# tempDAQ.net
KiCad netlist of a schematic drawn in EAGLE
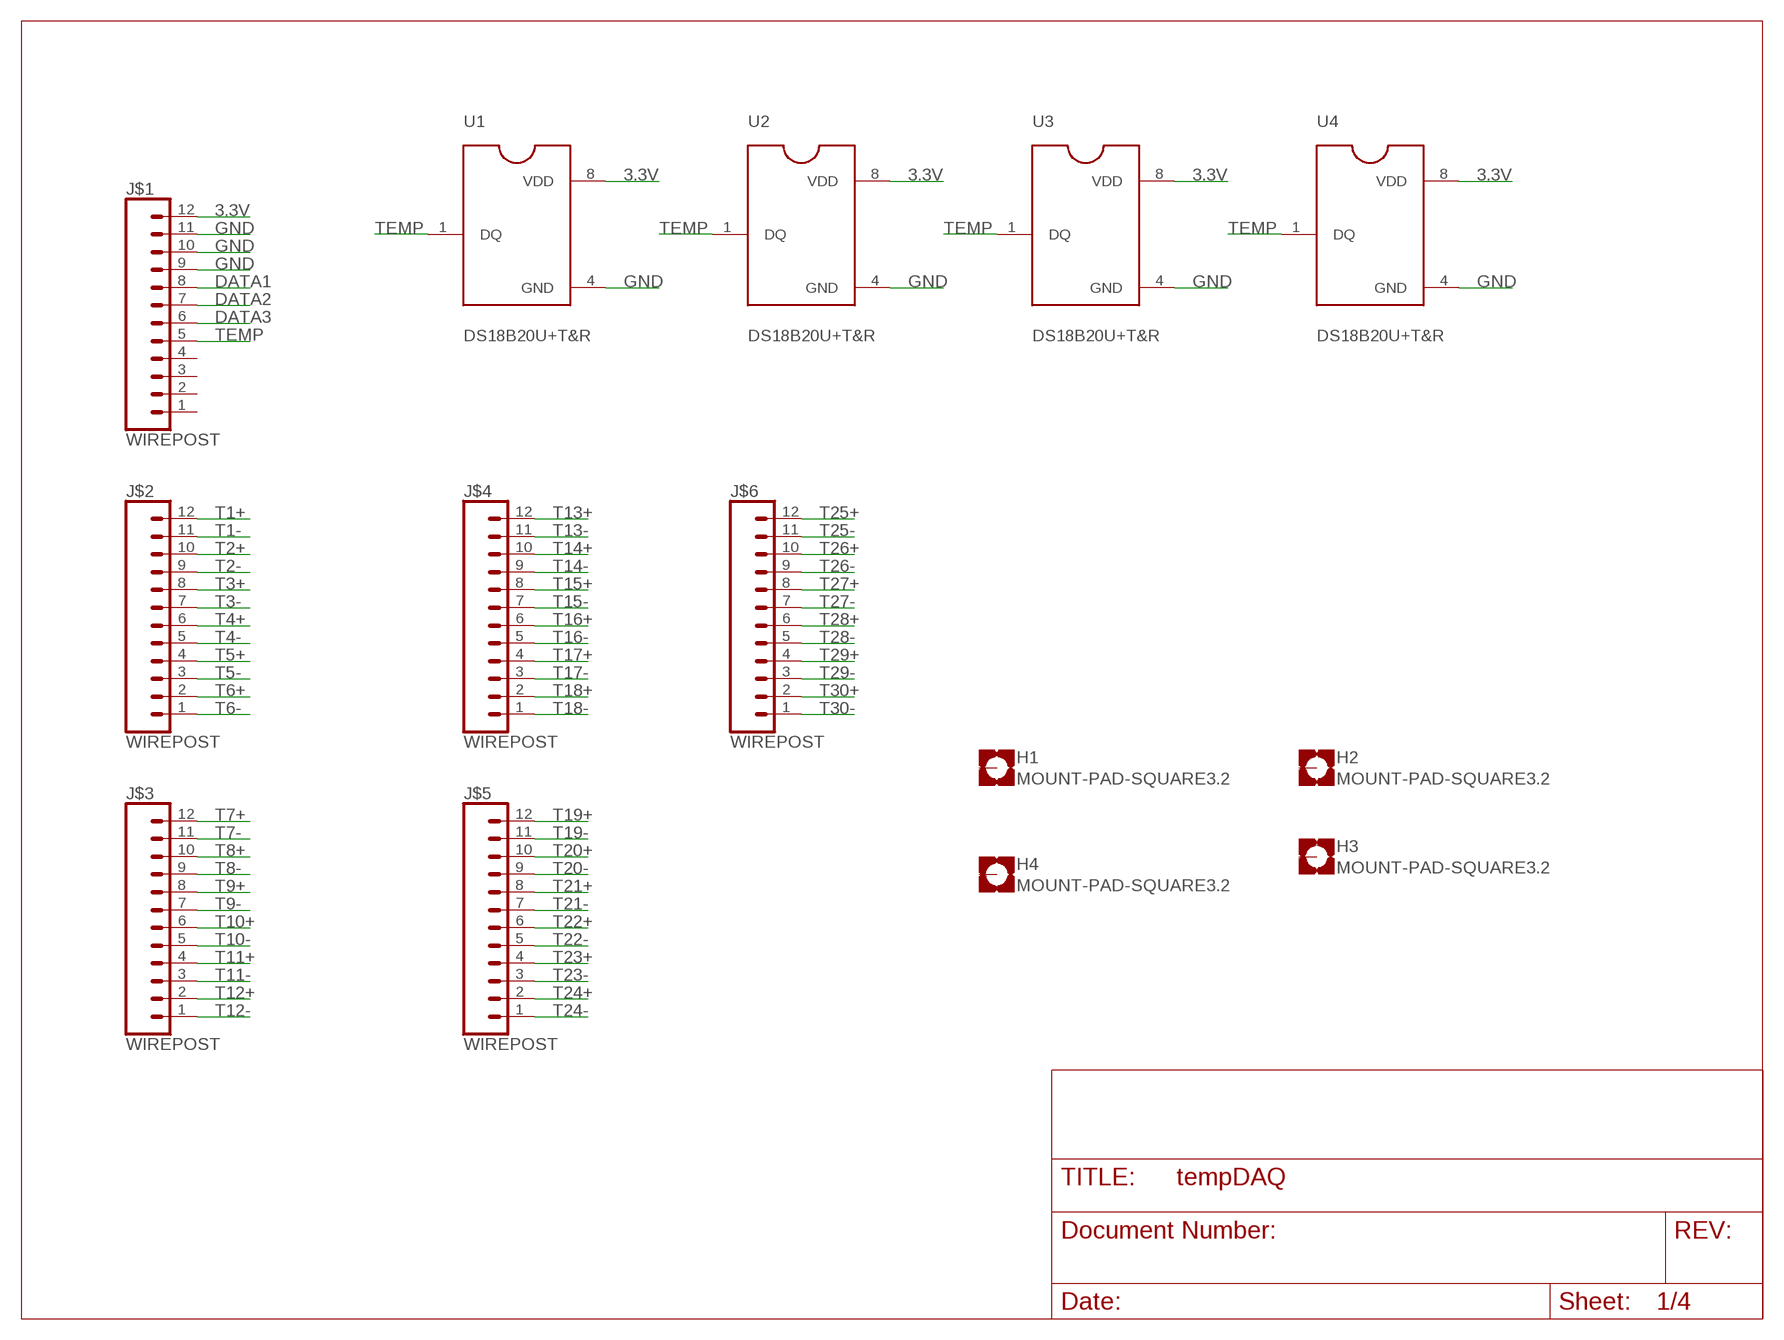
[diagram p0: schematic, sheet 1]
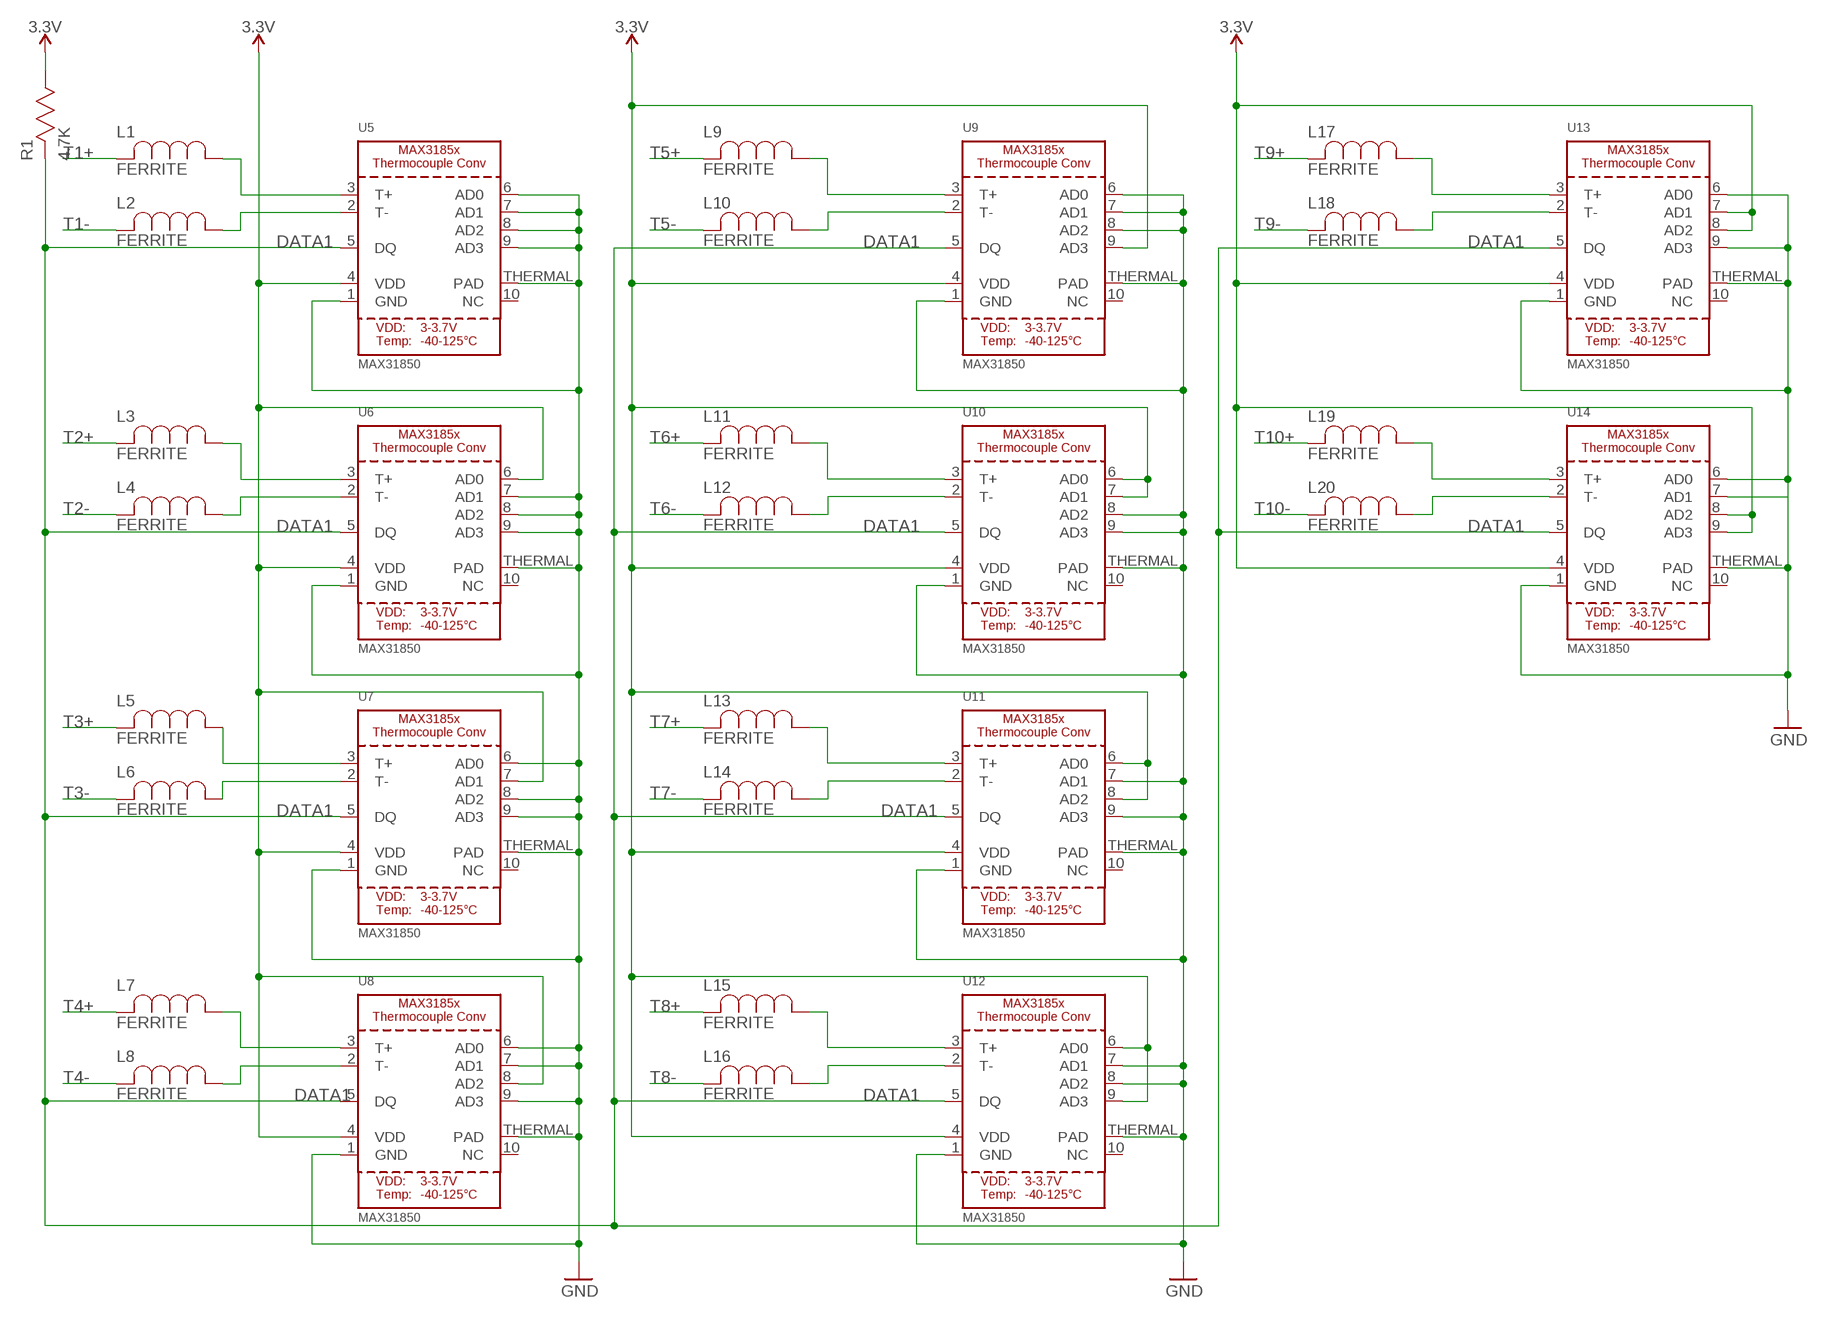
[diagram p1: schematic, sheet 2]
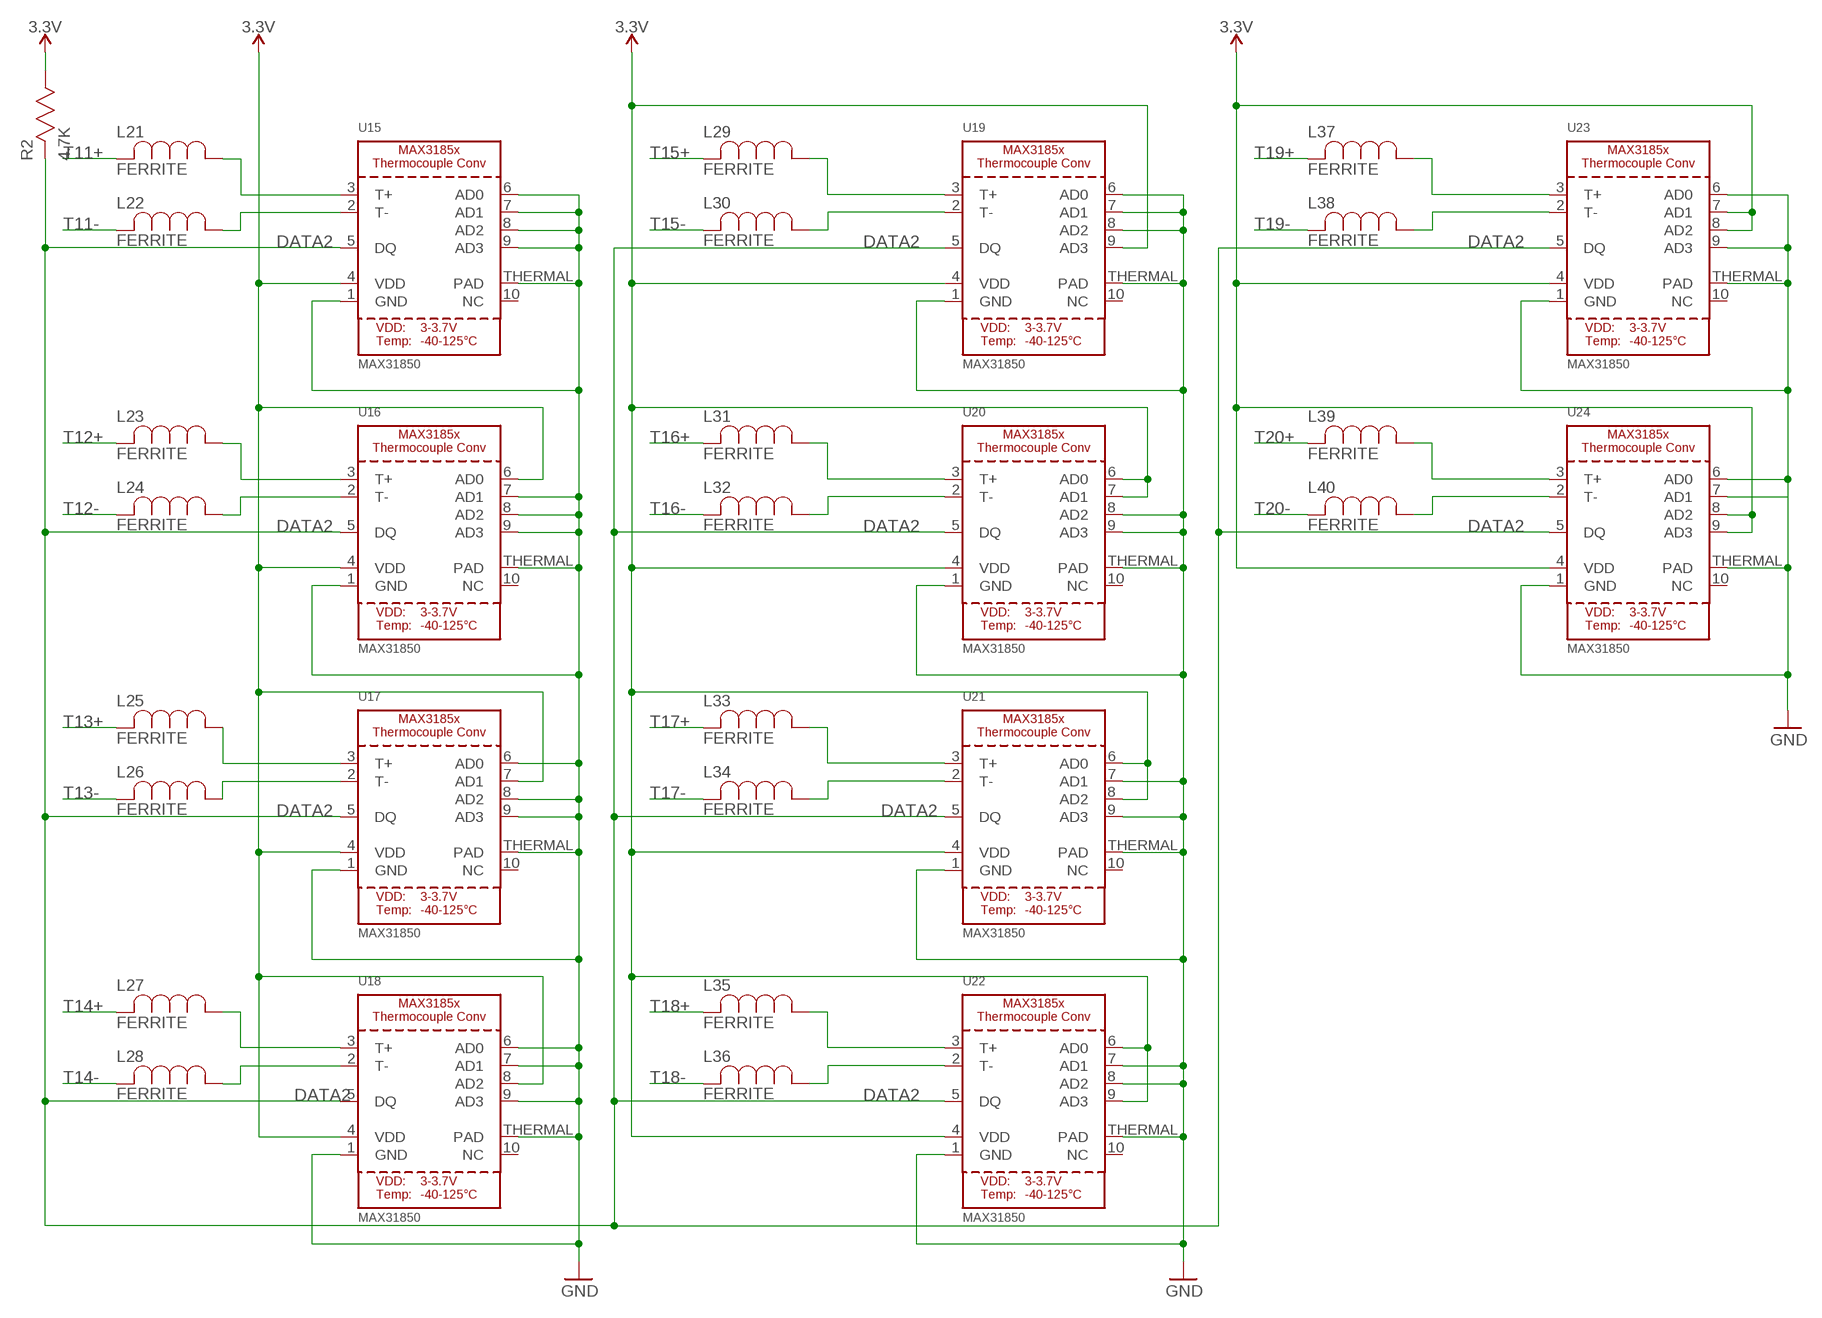
[diagram p2: schematic, sheet 3]
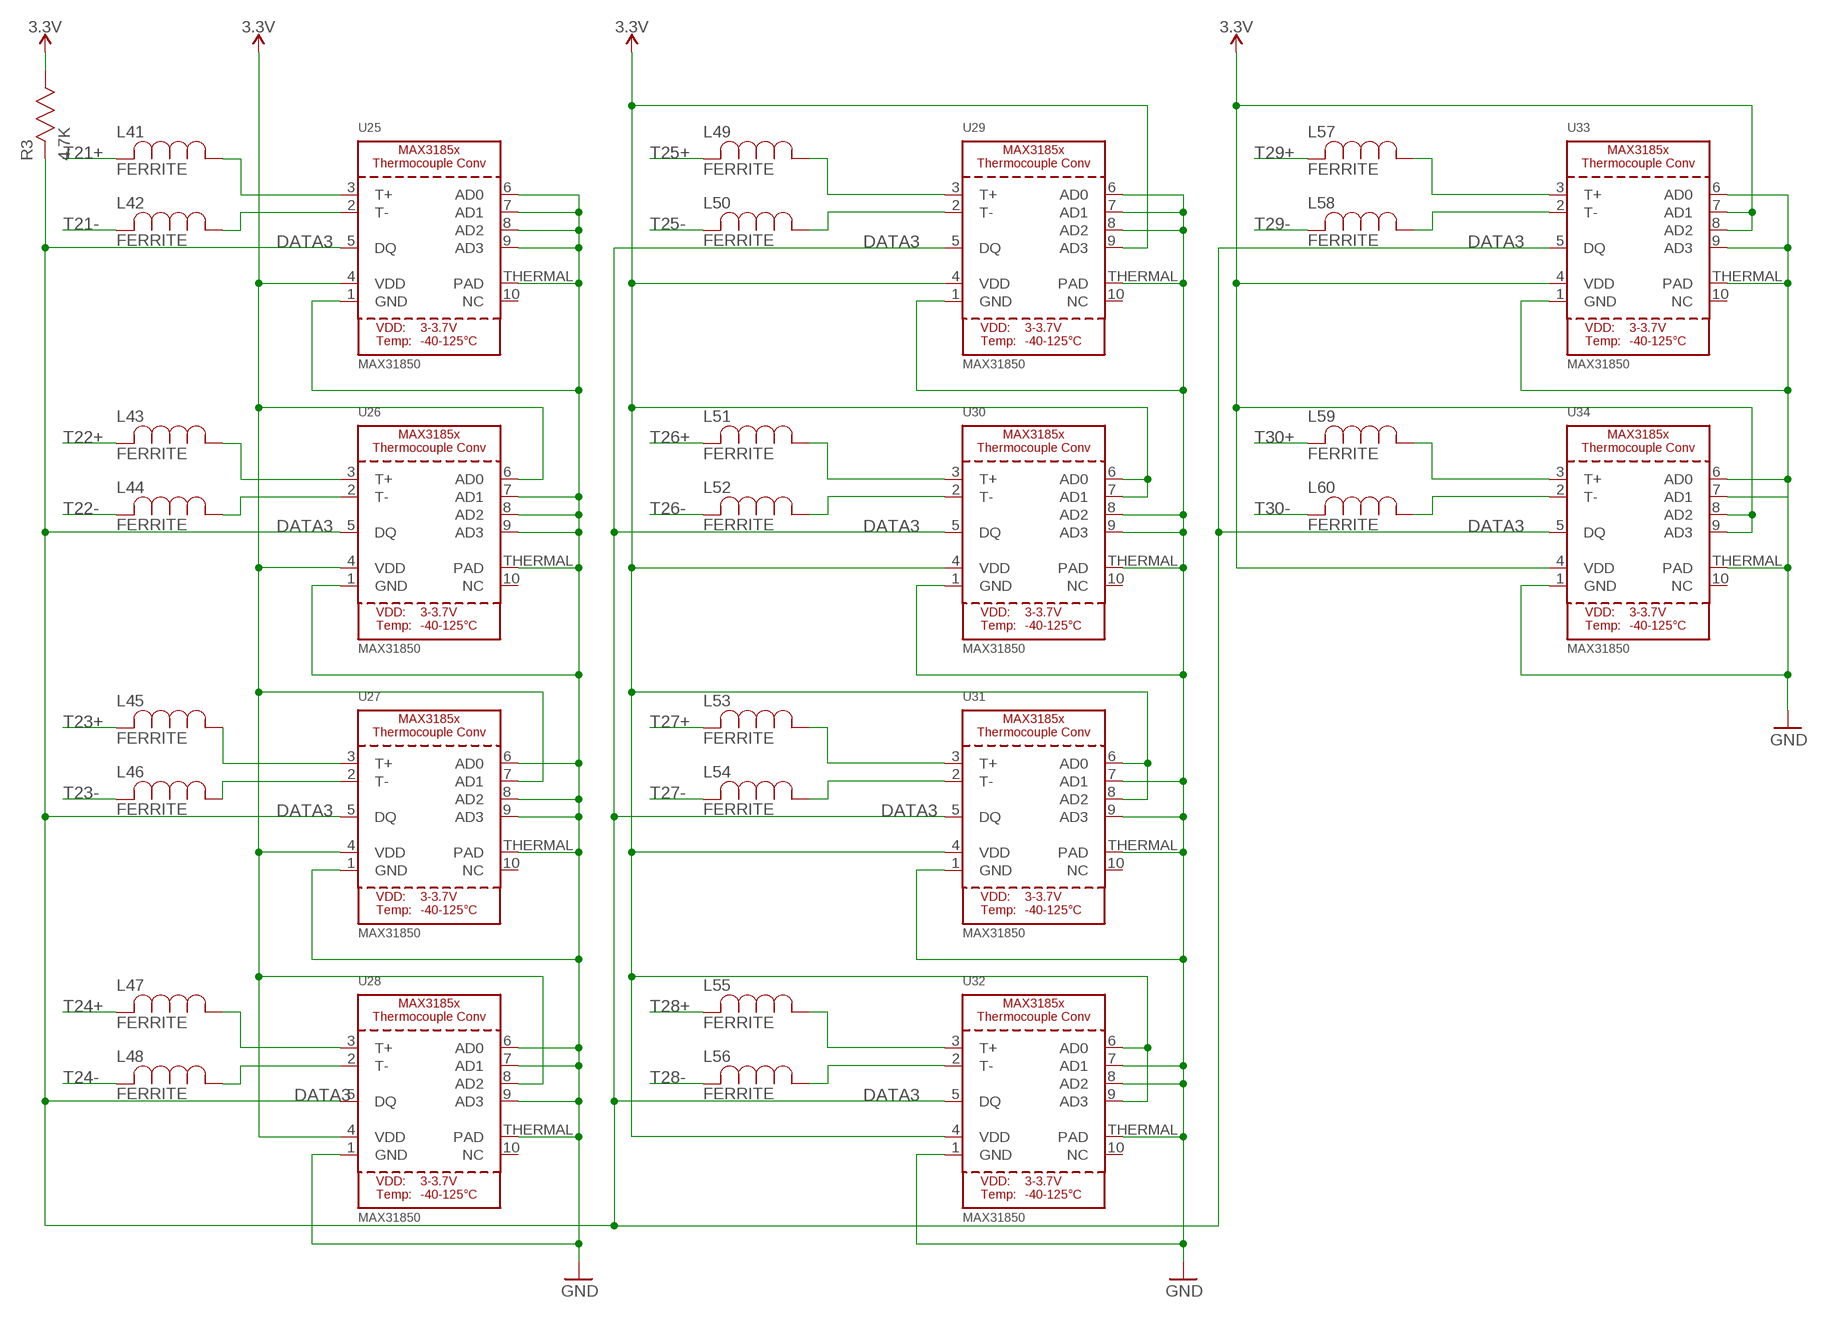
[diagram p3: schematic, sheet 4]

(export (version "E")
  (design (tool "Eeschema 10.0.6"))
  (components
    (comp (ref "L21")
      (value "FERRITE")
      (footprint "eagle-import:IND_BOURNS_MH2029")
      (fields (field (name "MANUFACTURER_PART_NUMBER") "MH2029300Y"))
      (libsource (lib "eagle-import") (part "FERRITE"))
    )
    (comp (ref "L22")
      (value "FERRITE")
      (footprint "eagle-import:IND_BOURNS_MH2029")
      (fields (field (name "MANUFACTURER_PART_NUMBER") "MH2029300Y"))
      (libsource (lib "eagle-import") (part "FERRITE"))
    )
    (comp (ref "L23")
      (value "FERRITE")
      (footprint "eagle-import:IND_BOURNS_MH2029")
      (fields (field (name "MANUFACTURER_PART_NUMBER") "MH2029300Y"))
      (libsource (lib "eagle-import") (part "FERRITE"))
    )
    (comp (ref "L24")
      (value "FERRITE")
      (footprint "eagle-import:IND_BOURNS_MH2029")
      (fields (field (name "MANUFACTURER_PART_NUMBER") "MH2029300Y"))
      (libsource (lib "eagle-import") (part "FERRITE"))
    )
    (comp (ref "L25")
      (value "FERRITE")
      (footprint "eagle-import:IND_BOURNS_MH2029")
      (fields (field (name "MANUFACTURER_PART_NUMBER") "MH2029300Y"))
      (libsource (lib "eagle-import") (part "FERRITE"))
    )
    (comp (ref "L26")
      (value "FERRITE")
      (footprint "eagle-import:IND_BOURNS_MH2029")
      (fields (field (name "MANUFACTURER_PART_NUMBER") "MH2029300Y"))
      (libsource (lib "eagle-import") (part "FERRITE"))
    )
    (comp (ref "L27")
      (value "FERRITE")
      (footprint "eagle-import:IND_BOURNS_MH2029")
      (fields (field (name "MANUFACTURER_PART_NUMBER") "MH2029300Y"))
      (libsource (lib "eagle-import") (part "FERRITE"))
    )
    (comp (ref "L28")
      (value "FERRITE")
      (footprint "eagle-import:IND_BOURNS_MH2029")
      (fields (field (name "MANUFACTURER_PART_NUMBER") "MH2029300Y"))
      (libsource (lib "eagle-import") (part "FERRITE"))
    )
    (comp (ref "L29")
      (value "FERRITE")
      (footprint "eagle-import:IND_BOURNS_MH2029")
      (fields (field (name "MANUFACTURER_PART_NUMBER") "MH2029300Y"))
      (libsource (lib "eagle-import") (part "FERRITE"))
    )
    (comp (ref "L30")
      (value "FERRITE")
      (footprint "eagle-import:IND_BOURNS_MH2029")
      (fields (field (name "MANUFACTURER_PART_NUMBER") "MH2029300Y"))
      (libsource (lib "eagle-import") (part "FERRITE"))
    )
    (comp (ref "L31")
      (value "FERRITE")
      (footprint "eagle-import:IND_BOURNS_MH2029")
      (fields (field (name "MANUFACTURER_PART_NUMBER") "MH2029300Y"))
      (libsource (lib "eagle-import") (part "FERRITE"))
    )
    (comp (ref "L32")
      (value "FERRITE")
      (footprint "eagle-import:IND_BOURNS_MH2029")
      (fields (field (name "MANUFACTURER_PART_NUMBER") "MH2029300Y"))
      (libsource (lib "eagle-import") (part "FERRITE"))
    )
    (comp (ref "L33")
      (value "FERRITE")
      (footprint "eagle-import:IND_BOURNS_MH2029")
      (fields (field (name "MANUFACTURER_PART_NUMBER") "MH2029300Y"))
      (libsource (lib "eagle-import") (part "FERRITE"))
    )
    (comp (ref "L34")
      (value "FERRITE")
      (footprint "eagle-import:IND_BOURNS_MH2029")
      (fields (field (name "MANUFACTURER_PART_NUMBER") "MH2029300Y"))
      (libsource (lib "eagle-import") (part "FERRITE"))
    )
    (comp (ref "L35")
      (value "FERRITE")
      (footprint "eagle-import:IND_BOURNS_MH2029")
      (fields (field (name "MANUFACTURER_PART_NUMBER") "MH2029300Y"))
      (libsource (lib "eagle-import") (part "FERRITE"))
    )
    (comp (ref "L36")
      (value "FERRITE")
      (footprint "eagle-import:IND_BOURNS_MH2029")
      (fields (field (name "MANUFACTURER_PART_NUMBER") "MH2029300Y"))
      (libsource (lib "eagle-import") (part "FERRITE"))
    )
    (comp (ref "L37")
      (value "FERRITE")
      (footprint "eagle-import:IND_BOURNS_MH2029")
      (fields (field (name "MANUFACTURER_PART_NUMBER") "MH2029300Y"))
      (libsource (lib "eagle-import") (part "FERRITE"))
    )
    (comp (ref "L38")
      (value "FERRITE")
      (footprint "eagle-import:IND_BOURNS_MH2029")
      (fields (field (name "MANUFACTURER_PART_NUMBER") "MH2029300Y"))
      (libsource (lib "eagle-import") (part "FERRITE"))
    )
    (comp (ref "L39")
      (value "FERRITE")
      (footprint "eagle-import:IND_BOURNS_MH2029")
      (fields (field (name "MANUFACTURER_PART_NUMBER") "MH2029300Y"))
      (libsource (lib "eagle-import") (part "FERRITE"))
    )
    (comp (ref "L40")
      (value "FERRITE")
      (footprint "eagle-import:IND_BOURNS_MH2029")
      (fields (field (name "MANUFACTURER_PART_NUMBER") "MH2029300Y"))
      (libsource (lib "eagle-import") (part "FERRITE"))
    )
    (comp (ref "R2")
      (value "4.7K")
      (footprint "eagle-import:RC0603N")
      (libsource (lib "eagle-import") (part "RES_4_7K"))
    )
    (comp (ref "U15")
      (value "MAX31850")
      (footprint "eagle-import:TDFN10_3X4MM")
      (libsource (lib "eagle-import") (part "MAX3185X"))
    )
    (comp (ref "U16")
      (value "MAX31850")
      (footprint "eagle-import:TDFN10_3X4MM")
      (libsource (lib "eagle-import") (part "MAX3185X"))
    )
    (comp (ref "U17")
      (value "MAX31850")
      (footprint "eagle-import:TDFN10_3X4MM")
      (libsource (lib "eagle-import") (part "MAX3185X"))
    )
    (comp (ref "U18")
      (value "MAX31850")
      (footprint "eagle-import:TDFN10_3X4MM")
      (libsource (lib "eagle-import") (part "MAX3185X"))
    )
    (comp (ref "U19")
      (value "MAX31850")
      (footprint "eagle-import:TDFN10_3X4MM")
      (libsource (lib "eagle-import") (part "MAX3185X"))
    )
    (comp (ref "U20")
      (value "MAX31850")
      (footprint "eagle-import:TDFN10_3X4MM")
      (libsource (lib "eagle-import") (part "MAX3185X"))
    )
    (comp (ref "U21")
      (value "MAX31850")
      (footprint "eagle-import:TDFN10_3X4MM")
      (libsource (lib "eagle-import") (part "MAX3185X"))
    )
    (comp (ref "U22")
      (value "MAX31850")
      (footprint "eagle-import:TDFN10_3X4MM")
      (libsource (lib "eagle-import") (part "MAX3185X"))
    )
    (comp (ref "U23")
      (value "MAX31850")
      (footprint "eagle-import:TDFN10_3X4MM")
      (libsource (lib "eagle-import") (part "MAX3185X"))
    )
    (comp (ref "U24")
      (value "MAX31850")
      (footprint "eagle-import:TDFN10_3X4MM")
      (libsource (lib "eagle-import") (part "MAX3185X"))
    )
    (comp (ref "L41")
      (value "FERRITE")
      (footprint "eagle-import:IND_BOURNS_MH2029")
      (fields (field (name "MANUFACTURER_PART_NUMBER") "MH2029300Y"))
      (libsource (lib "eagle-import") (part "FERRITE"))
    )
    (comp (ref "L42")
      (value "FERRITE")
      (footprint "eagle-import:IND_BOURNS_MH2029")
      (fields (field (name "MANUFACTURER_PART_NUMBER") "MH2029300Y"))
      (libsource (lib "eagle-import") (part "FERRITE"))
    )
    (comp (ref "L43")
      (value "FERRITE")
      (footprint "eagle-import:IND_BOURNS_MH2029")
      (fields (field (name "MANUFACTURER_PART_NUMBER") "MH2029300Y"))
      (libsource (lib "eagle-import") (part "FERRITE"))
    )
    (comp (ref "L44")
      (value "FERRITE")
      (footprint "eagle-import:IND_BOURNS_MH2029")
      (fields (field (name "MANUFACTURER_PART_NUMBER") "MH2029300Y"))
      (libsource (lib "eagle-import") (part "FERRITE"))
    )
    (comp (ref "L45")
      (value "FERRITE")
      (footprint "eagle-import:IND_BOURNS_MH2029")
      (fields (field (name "MANUFACTURER_PART_NUMBER") "MH2029300Y"))
      (libsource (lib "eagle-import") (part "FERRITE"))
    )
    (comp (ref "L46")
      (value "FERRITE")
      (footprint "eagle-import:IND_BOURNS_MH2029")
      (fields (field (name "MANUFACTURER_PART_NUMBER") "MH2029300Y"))
      (libsource (lib "eagle-import") (part "FERRITE"))
    )
    (comp (ref "L47")
      (value "FERRITE")
      (footprint "eagle-import:IND_BOURNS_MH2029")
      (fields (field (name "MANUFACTURER_PART_NUMBER") "MH2029300Y"))
      (libsource (lib "eagle-import") (part "FERRITE"))
    )
    (comp (ref "L48")
      (value "FERRITE")
      (footprint "eagle-import:IND_BOURNS_MH2029")
      (fields (field (name "MANUFACTURER_PART_NUMBER") "MH2029300Y"))
      (libsource (lib "eagle-import") (part "FERRITE"))
    )
    (comp (ref "L49")
      (value "FERRITE")
      (footprint "eagle-import:IND_BOURNS_MH2029")
      (fields (field (name "MANUFACTURER_PART_NUMBER") "MH2029300Y"))
      (libsource (lib "eagle-import") (part "FERRITE"))
    )
    (comp (ref "L50")
      (value "FERRITE")
      (footprint "eagle-import:IND_BOURNS_MH2029")
      (fields (field (name "MANUFACTURER_PART_NUMBER") "MH2029300Y"))
      (libsource (lib "eagle-import") (part "FERRITE"))
    )
    (comp (ref "L51")
      (value "FERRITE")
      (footprint "eagle-import:IND_BOURNS_MH2029")
      (fields (field (name "MANUFACTURER_PART_NUMBER") "MH2029300Y"))
      (libsource (lib "eagle-import") (part "FERRITE"))
    )
    (comp (ref "L52")
      (value "FERRITE")
      (footprint "eagle-import:IND_BOURNS_MH2029")
      (fields (field (name "MANUFACTURER_PART_NUMBER") "MH2029300Y"))
      (libsource (lib "eagle-import") (part "FERRITE"))
    )
    (comp (ref "L53")
      (value "FERRITE")
      (footprint "eagle-import:IND_BOURNS_MH2029")
      (fields (field (name "MANUFACTURER_PART_NUMBER") "MH2029300Y"))
      (libsource (lib "eagle-import") (part "FERRITE"))
    )
    (comp (ref "L54")
      (value "FERRITE")
      (footprint "eagle-import:IND_BOURNS_MH2029")
      (fields (field (name "MANUFACTURER_PART_NUMBER") "MH2029300Y"))
      (libsource (lib "eagle-import") (part "FERRITE"))
    )
    (comp (ref "L55")
      (value "FERRITE")
      (footprint "eagle-import:IND_BOURNS_MH2029")
      (fields (field (name "MANUFACTURER_PART_NUMBER") "MH2029300Y"))
      (libsource (lib "eagle-import") (part "FERRITE"))
    )
    (comp (ref "L56")
      (value "FERRITE")
      (footprint "eagle-import:IND_BOURNS_MH2029")
      (fields (field (name "MANUFACTURER_PART_NUMBER") "MH2029300Y"))
      (libsource (lib "eagle-import") (part "FERRITE"))
    )
    (comp (ref "L57")
      (value "FERRITE")
      (footprint "eagle-import:IND_BOURNS_MH2029")
      (fields (field (name "MANUFACTURER_PART_NUMBER") "MH2029300Y"))
      (libsource (lib "eagle-import") (part "FERRITE"))
    )
    (comp (ref "L58")
      (value "FERRITE")
      (footprint "eagle-import:IND_BOURNS_MH2029")
      (fields (field (name "MANUFACTURER_PART_NUMBER") "MH2029300Y"))
      (libsource (lib "eagle-import") (part "FERRITE"))
    )
    (comp (ref "L59")
      (value "FERRITE")
      (footprint "eagle-import:IND_BOURNS_MH2029")
      (fields (field (name "MANUFACTURER_PART_NUMBER") "MH2029300Y"))
      (libsource (lib "eagle-import") (part "FERRITE"))
    )
    (comp (ref "L60")
      (value "FERRITE")
      (footprint "eagle-import:IND_BOURNS_MH2029")
      (fields (field (name "MANUFACTURER_PART_NUMBER") "MH2029300Y"))
      (libsource (lib "eagle-import") (part "FERRITE"))
    )
    (comp (ref "R3")
      (value "4.7K")
      (footprint "eagle-import:RC0603N")
      (libsource (lib "eagle-import") (part "RES_4_7K"))
    )
    (comp (ref "U25")
      (value "MAX31850")
      (footprint "eagle-import:TDFN10_3X4MM")
      (libsource (lib "eagle-import") (part "MAX3185X"))
    )
    (comp (ref "U26")
      (value "MAX31850")
      (footprint "eagle-import:TDFN10_3X4MM")
      (libsource (lib "eagle-import") (part "MAX3185X"))
    )
    (comp (ref "U27")
      (value "MAX31850")
      (footprint "eagle-import:TDFN10_3X4MM")
      (libsource (lib "eagle-import") (part "MAX3185X"))
    )
    (comp (ref "U28")
      (value "MAX31850")
      (footprint "eagle-import:TDFN10_3X4MM")
      (libsource (lib "eagle-import") (part "MAX3185X"))
    )
    (comp (ref "U29")
      (value "MAX31850")
      (footprint "eagle-import:TDFN10_3X4MM")
      (libsource (lib "eagle-import") (part "MAX3185X"))
    )
    (comp (ref "U30")
      (value "MAX31850")
      (footprint "eagle-import:TDFN10_3X4MM")
      (libsource (lib "eagle-import") (part "MAX3185X"))
    )
    (comp (ref "U31")
      (value "MAX31850")
      (footprint "eagle-import:TDFN10_3X4MM")
      (libsource (lib "eagle-import") (part "MAX3185X"))
    )
    (comp (ref "U32")
      (value "MAX31850")
      (footprint "eagle-import:TDFN10_3X4MM")
      (libsource (lib "eagle-import") (part "MAX3185X"))
    )
    (comp (ref "U33")
      (value "MAX31850")
      (footprint "eagle-import:TDFN10_3X4MM")
      (libsource (lib "eagle-import") (part "MAX3185X"))
    )
    (comp (ref "U34")
      (value "MAX31850")
      (footprint "eagle-import:TDFN10_3X4MM")
      (libsource (lib "eagle-import") (part "MAX3185X"))
    )
    (comp (ref "H1")
      (value "MOUNT-PAD-SQUARE3.2")
      (footprint "eagle-import:3,2-PAD-SQUARE")
      (libsource (lib "eagle-import") (part "MOUNT-PAD-SQUARE3.2"))
    )
    (comp (ref "H2")
      (value "MOUNT-PAD-SQUARE3.2")
      (footprint "eagle-import:3,2-PAD-SQUARE")
      (libsource (lib "eagle-import") (part "MOUNT-PAD-SQUARE3.2"))
    )
    (comp (ref "H3")
      (value "MOUNT-PAD-SQUARE3.2")
      (footprint "eagle-import:3,2-PAD-SQUARE")
      (libsource (lib "eagle-import") (part "MOUNT-PAD-SQUARE3.2"))
    )
    (comp (ref "H4")
      (value "MOUNT-PAD-SQUARE3.2")
      (footprint "eagle-import:3,2-PAD-SQUARE")
      (libsource (lib "eagle-import") (part "MOUNT-PAD-SQUARE3.2"))
    )
    (comp (ref "J$1")
      (value "WIREPOST")
      (footprint "eagle-import:WIREWRAPPOST")
      (libsource (lib "eagle-import") (part "WIREPOST"))
    )
    (comp (ref "J$2")
      (value "WIREPOST")
      (footprint "eagle-import:WIREWRAPPOST")
      (libsource (lib "eagle-import") (part "WIREPOST"))
    )
    (comp (ref "J$3")
      (value "WIREPOST")
      (footprint "eagle-import:WIREWRAPPOST")
      (libsource (lib "eagle-import") (part "WIREPOST"))
    )
    (comp (ref "J$4")
      (value "WIREPOST")
      (footprint "eagle-import:WIREWRAPPOST")
      (libsource (lib "eagle-import") (part "WIREPOST"))
    )
    (comp (ref "J$5")
      (value "WIREPOST")
      (footprint "eagle-import:WIREWRAPPOST")
      (libsource (lib "eagle-import") (part "WIREPOST"))
    )
    (comp (ref "J$6")
      (value "WIREPOST")
      (footprint "eagle-import:WIREWRAPPOST")
      (libsource (lib "eagle-import") (part "WIREPOST"))
    )
    (comp (ref "U1")
      (value "DS18B20U+T&R")
      (footprint "eagle-import:SOP65P500X110-8N")
      (fields (field (name "MF") "Maxim Integrated") (field (name "MP") "DS18B20U+T&amp;R"))
      (libsource (lib "eagle-import") (part "DS18B20U+T&R"))
    )
    (comp (ref "U2")
      (value "DS18B20U+T&R")
      (footprint "eagle-import:SOP65P500X110-8N")
      (fields (field (name "MF") "Maxim Integrated") (field (name "MP") "DS18B20U+T&amp;R"))
      (libsource (lib "eagle-import") (part "DS18B20U+T&R"))
    )
    (comp (ref "U3")
      (value "DS18B20U+T&R")
      (footprint "eagle-import:SOP65P500X110-8N")
      (fields (field (name "MF") "Maxim Integrated") (field (name "MP") "DS18B20U+T&amp;R"))
      (libsource (lib "eagle-import") (part "DS18B20U+T&R"))
    )
    (comp (ref "U4")
      (value "DS18B20U+T&R")
      (footprint "eagle-import:SOP65P500X110-8N")
      (fields (field (name "MF") "Maxim Integrated") (field (name "MP") "DS18B20U+T&amp;R"))
      (libsource (lib "eagle-import") (part "DS18B20U+T&R"))
    )
    (comp (ref "L1")
      (value "FERRITE")
      (footprint "eagle-import:IND_BOURNS_MH2029")
      (fields (field (name "MANUFACTURER_PART_NUMBER") "MH2029300Y"))
      (libsource (lib "eagle-import") (part "FERRITE"))
    )
    (comp (ref "L2")
      (value "FERRITE")
      (footprint "eagle-import:IND_BOURNS_MH2029")
      (fields (field (name "MANUFACTURER_PART_NUMBER") "MH2029300Y"))
      (libsource (lib "eagle-import") (part "FERRITE"))
    )
    (comp (ref "L3")
      (value "FERRITE")
      (footprint "eagle-import:IND_BOURNS_MH2029")
      (fields (field (name "MANUFACTURER_PART_NUMBER") "MH2029300Y"))
      (libsource (lib "eagle-import") (part "FERRITE"))
    )
    (comp (ref "L4")
      (value "FERRITE")
      (footprint "eagle-import:IND_BOURNS_MH2029")
      (fields (field (name "MANUFACTURER_PART_NUMBER") "MH2029300Y"))
      (libsource (lib "eagle-import") (part "FERRITE"))
    )
    (comp (ref "L5")
      (value "FERRITE")
      (footprint "eagle-import:IND_BOURNS_MH2029")
      (fields (field (name "MANUFACTURER_PART_NUMBER") "MH2029300Y"))
      (libsource (lib "eagle-import") (part "FERRITE"))
    )
    (comp (ref "L6")
      (value "FERRITE")
      (footprint "eagle-import:IND_BOURNS_MH2029")
      (fields (field (name "MANUFACTURER_PART_NUMBER") "MH2029300Y"))
      (libsource (lib "eagle-import") (part "FERRITE"))
    )
    (comp (ref "L7")
      (value "FERRITE")
      (footprint "eagle-import:IND_BOURNS_MH2029")
      (fields (field (name "MANUFACTURER_PART_NUMBER") "MH2029300Y"))
      (libsource (lib "eagle-import") (part "FERRITE"))
    )
    (comp (ref "L8")
      (value "FERRITE")
      (footprint "eagle-import:IND_BOURNS_MH2029")
      (fields (field (name "MANUFACTURER_PART_NUMBER") "MH2029300Y"))
      (libsource (lib "eagle-import") (part "FERRITE"))
    )
    (comp (ref "L9")
      (value "FERRITE")
      (footprint "eagle-import:IND_BOURNS_MH2029")
      (fields (field (name "MANUFACTURER_PART_NUMBER") "MH2029300Y"))
      (libsource (lib "eagle-import") (part "FERRITE"))
    )
    (comp (ref "L10")
      (value "FERRITE")
      (footprint "eagle-import:IND_BOURNS_MH2029")
      (fields (field (name "MANUFACTURER_PART_NUMBER") "MH2029300Y"))
      (libsource (lib "eagle-import") (part "FERRITE"))
    )
    (comp (ref "L11")
      (value "FERRITE")
      (footprint "eagle-import:IND_BOURNS_MH2029")
      (fields (field (name "MANUFACTURER_PART_NUMBER") "MH2029300Y"))
      (libsource (lib "eagle-import") (part "FERRITE"))
    )
    (comp (ref "L12")
      (value "FERRITE")
      (footprint "eagle-import:IND_BOURNS_MH2029")
      (fields (field (name "MANUFACTURER_PART_NUMBER") "MH2029300Y"))
      (libsource (lib "eagle-import") (part "FERRITE"))
    )
    (comp (ref "L13")
      (value "FERRITE")
      (footprint "eagle-import:IND_BOURNS_MH2029")
      (fields (field (name "MANUFACTURER_PART_NUMBER") "MH2029300Y"))
      (libsource (lib "eagle-import") (part "FERRITE"))
    )
    (comp (ref "L14")
      (value "FERRITE")
      (footprint "eagle-import:IND_BOURNS_MH2029")
      (fields (field (name "MANUFACTURER_PART_NUMBER") "MH2029300Y"))
      (libsource (lib "eagle-import") (part "FERRITE"))
    )
    (comp (ref "L15")
      (value "FERRITE")
      (footprint "eagle-import:IND_BOURNS_MH2029")
      (fields (field (name "MANUFACTURER_PART_NUMBER") "MH2029300Y"))
      (libsource (lib "eagle-import") (part "FERRITE"))
    )
    (comp (ref "L16")
      (value "FERRITE")
      (footprint "eagle-import:IND_BOURNS_MH2029")
      (fields (field (name "MANUFACTURER_PART_NUMBER") "MH2029300Y"))
      (libsource (lib "eagle-import") (part "FERRITE"))
    )
    (comp (ref "L17")
      (value "FERRITE")
      (footprint "eagle-import:IND_BOURNS_MH2029")
      (fields (field (name "MANUFACTURER_PART_NUMBER") "MH2029300Y"))
      (libsource (lib "eagle-import") (part "FERRITE"))
    )
    (comp (ref "L18")
      (value "FERRITE")
      (footprint "eagle-import:IND_BOURNS_MH2029")
      (fields (field (name "MANUFACTURER_PART_NUMBER") "MH2029300Y"))
      (libsource (lib "eagle-import") (part "FERRITE"))
    )
    (comp (ref "L19")
      (value "FERRITE")
      (footprint "eagle-import:IND_BOURNS_MH2029")
      (fields (field (name "MANUFACTURER_PART_NUMBER") "MH2029300Y"))
      (libsource (lib "eagle-import") (part "FERRITE"))
    )
    (comp (ref "L20")
      (value "FERRITE")
      (footprint "eagle-import:IND_BOURNS_MH2029")
      (fields (field (name "MANUFACTURER_PART_NUMBER") "MH2029300Y"))
      (libsource (lib "eagle-import") (part "FERRITE"))
    )
    (comp (ref "R1")
      (value "4.7K")
      (footprint "eagle-import:RC0603N")
      (libsource (lib "eagle-import") (part "RES_4_7K"))
    )
    (comp (ref "U5")
      (value "MAX31850")
      (footprint "eagle-import:TDFN10_3X4MM")
      (libsource (lib "eagle-import") (part "MAX3185X"))
    )
    (comp (ref "U6")
      (value "MAX31850")
      (footprint "eagle-import:TDFN10_3X4MM")
      (libsource (lib "eagle-import") (part "MAX3185X"))
    )
    (comp (ref "U7")
      (value "MAX31850")
      (footprint "eagle-import:TDFN10_3X4MM")
      (libsource (lib "eagle-import") (part "MAX3185X"))
    )
    (comp (ref "U8")
      (value "MAX31850")
      (footprint "eagle-import:TDFN10_3X4MM")
      (libsource (lib "eagle-import") (part "MAX3185X"))
    )
    (comp (ref "U9")
      (value "MAX31850")
      (footprint "eagle-import:TDFN10_3X4MM")
      (libsource (lib "eagle-import") (part "MAX3185X"))
    )
    (comp (ref "U10")
      (value "MAX31850")
      (footprint "eagle-import:TDFN10_3X4MM")
      (libsource (lib "eagle-import") (part "MAX3185X"))
    )
    (comp (ref "U11")
      (value "MAX31850")
      (footprint "eagle-import:TDFN10_3X4MM")
      (libsource (lib "eagle-import") (part "MAX3185X"))
    )
    (comp (ref "U12")
      (value "MAX31850")
      (footprint "eagle-import:TDFN10_3X4MM")
      (libsource (lib "eagle-import") (part "MAX3185X"))
    )
    (comp (ref "U13")
      (value "MAX31850")
      (footprint "eagle-import:TDFN10_3X4MM")
      (libsource (lib "eagle-import") (part "MAX3185X"))
    )
    (comp (ref "U14")
      (value "MAX31850")
      (footprint "eagle-import:TDFN10_3X4MM")
      (libsource (lib "eagle-import") (part "MAX3185X"))
    )
  )
  (nets
    (net (code "1") (name "3.3V") (class "Default")
      (node (ref "J$1") (pin "12") (pinfunction "12_12") (pintype "passive"))
      (node (ref "R1") (pin "1") (pinfunction "11_1") (pintype "passive"))
      (node (ref "R2") (pin "1") (pinfunction "11_1") (pintype "passive"))
      (node (ref "R3") (pin "1") (pinfunction "11_1") (pintype "passive"))
      (node (ref "U1") (pin "8") (pinfunction "VDD_8") (pintype "power_in"))
      (node (ref "U10") (pin "4") (pinfunction "VDD_4") (pintype "power_in"))
      (node (ref "U10") (pin "6") (pinfunction "AD0_6") (pintype "input"))
      (node (ref "U10") (pin "7") (pinfunction "AD1_7") (pintype "input"))
      (node (ref "U11") (pin "4") (pinfunction "VDD_4") (pintype "power_in"))
      (node (ref "U11") (pin "6") (pinfunction "AD0_6") (pintype "input"))
      (node (ref "U11") (pin "8") (pinfunction "AD2_8") (pintype "input"))
      (node (ref "U12") (pin "4") (pinfunction "VDD_4") (pintype "power_in"))
      (node (ref "U12") (pin "6") (pinfunction "AD0_6") (pintype "input"))
      (node (ref "U12") (pin "9") (pinfunction "AD3_9") (pintype "input"))
      (node (ref "U13") (pin "4") (pinfunction "VDD_4") (pintype "power_in"))
      (node (ref "U13") (pin "7") (pinfunction "AD1_7") (pintype "input"))
      (node (ref "U13") (pin "8") (pinfunction "AD2_8") (pintype "input"))
      (node (ref "U14") (pin "4") (pinfunction "VDD_4") (pintype "power_in"))
      (node (ref "U14") (pin "8") (pinfunction "AD2_8") (pintype "input"))
      (node (ref "U14") (pin "9") (pinfunction "AD3_9") (pintype "input"))
      (node (ref "U15") (pin "4") (pinfunction "VDD_4") (pintype "power_in"))
      (node (ref "U16") (pin "4") (pinfunction "VDD_4") (pintype "power_in"))
      (node (ref "U16") (pin "6") (pinfunction "AD0_6") (pintype "input"))
      (node (ref "U17") (pin "4") (pinfunction "VDD_4") (pintype "power_in"))
      (node (ref "U17") (pin "7") (pinfunction "AD1_7") (pintype "input"))
      (node (ref "U18") (pin "4") (pinfunction "VDD_4") (pintype "power_in"))
      (node (ref "U18") (pin "8") (pinfunction "AD2_8") (pintype "input"))
      (node (ref "U19") (pin "4") (pinfunction "VDD_4") (pintype "power_in"))
      (node (ref "U19") (pin "9") (pinfunction "AD3_9") (pintype "input"))
      (node (ref "U2") (pin "8") (pinfunction "VDD_8") (pintype "power_in"))
      (node (ref "U20") (pin "4") (pinfunction "VDD_4") (pintype "power_in"))
      (node (ref "U20") (pin "6") (pinfunction "AD0_6") (pintype "input"))
      (node (ref "U20") (pin "7") (pinfunction "AD1_7") (pintype "input"))
      (node (ref "U21") (pin "4") (pinfunction "VDD_4") (pintype "power_in"))
      (node (ref "U21") (pin "6") (pinfunction "AD0_6") (pintype "input"))
      (node (ref "U21") (pin "8") (pinfunction "AD2_8") (pintype "input"))
      (node (ref "U22") (pin "4") (pinfunction "VDD_4") (pintype "power_in"))
      (node (ref "U22") (pin "6") (pinfunction "AD0_6") (pintype "input"))
      (node (ref "U22") (pin "9") (pinfunction "AD3_9") (pintype "input"))
      (node (ref "U23") (pin "4") (pinfunction "VDD_4") (pintype "power_in"))
      (node (ref "U23") (pin "7") (pinfunction "AD1_7") (pintype "input"))
      (node (ref "U23") (pin "8") (pinfunction "AD2_8") (pintype "input"))
      (node (ref "U24") (pin "4") (pinfunction "VDD_4") (pintype "power_in"))
      (node (ref "U24") (pin "8") (pinfunction "AD2_8") (pintype "input"))
      (node (ref "U24") (pin "9") (pinfunction "AD3_9") (pintype "input"))
      (node (ref "U25") (pin "4") (pinfunction "VDD_4") (pintype "power_in"))
      (node (ref "U26") (pin "4") (pinfunction "VDD_4") (pintype "power_in"))
      (node (ref "U26") (pin "6") (pinfunction "AD0_6") (pintype "input"))
      (node (ref "U27") (pin "4") (pinfunction "VDD_4") (pintype "power_in"))
      (node (ref "U27") (pin "7") (pinfunction "AD1_7") (pintype "input"))
      (node (ref "U28") (pin "4") (pinfunction "VDD_4") (pintype "power_in"))
      (node (ref "U28") (pin "8") (pinfunction "AD2_8") (pintype "input"))
      (node (ref "U29") (pin "4") (pinfunction "VDD_4") (pintype "power_in"))
      (node (ref "U29") (pin "9") (pinfunction "AD3_9") (pintype "input"))
      (node (ref "U3") (pin "8") (pinfunction "VDD_8") (pintype "power_in"))
      (node (ref "U30") (pin "4") (pinfunction "VDD_4") (pintype "power_in"))
      (node (ref "U30") (pin "6") (pinfunction "AD0_6") (pintype "input"))
      (node (ref "U30") (pin "7") (pinfunction "AD1_7") (pintype "input"))
      (node (ref "U31") (pin "4") (pinfunction "VDD_4") (pintype "power_in"))
      (node (ref "U31") (pin "6") (pinfunction "AD0_6") (pintype "input"))
      (node (ref "U31") (pin "8") (pinfunction "AD2_8") (pintype "input"))
      (node (ref "U32") (pin "4") (pinfunction "VDD_4") (pintype "power_in"))
      (node (ref "U32") (pin "6") (pinfunction "AD0_6") (pintype "input"))
      (node (ref "U32") (pin "9") (pinfunction "AD3_9") (pintype "input"))
      (node (ref "U33") (pin "4") (pinfunction "VDD_4") (pintype "power_in"))
      (node (ref "U33") (pin "7") (pinfunction "AD1_7") (pintype "input"))
      (node (ref "U33") (pin "8") (pinfunction "AD2_8") (pintype "input"))
      (node (ref "U34") (pin "4") (pinfunction "VDD_4") (pintype "power_in"))
      (node (ref "U34") (pin "8") (pinfunction "AD2_8") (pintype "input"))
      (node (ref "U34") (pin "9") (pinfunction "AD3_9") (pintype "input"))
      (node (ref "U4") (pin "8") (pinfunction "VDD_8") (pintype "power_in"))
      (node (ref "U5") (pin "4") (pinfunction "VDD_4") (pintype "power_in"))
      (node (ref "U6") (pin "4") (pinfunction "VDD_4") (pintype "power_in"))
      (node (ref "U6") (pin "6") (pinfunction "AD0_6") (pintype "input"))
      (node (ref "U7") (pin "4") (pinfunction "VDD_4") (pintype "power_in"))
      (node (ref "U7") (pin "7") (pinfunction "AD1_7") (pintype "input"))
      (node (ref "U8") (pin "4") (pinfunction "VDD_4") (pintype "power_in"))
      (node (ref "U8") (pin "8") (pinfunction "AD2_8") (pintype "input"))
      (node (ref "U9") (pin "4") (pinfunction "VDD_4") (pintype "power_in"))
      (node (ref "U9") (pin "9") (pinfunction "AD3_9") (pintype "input"))
    )
    (net (code "2") (name "DATA1") (class "Default")
      (node (ref "J$1") (pin "8") (pinfunction "8_8") (pintype "passive"))
      (node (ref "R1") (pin "2") (pinfunction "22_2") (pintype "passive"))
      (node (ref "U10") (pin "5") (pinfunction "DQ_5") (pintype "bidirectional"))
      (node (ref "U11") (pin "5") (pinfunction "DQ_5") (pintype "bidirectional"))
      (node (ref "U12") (pin "5") (pinfunction "DQ_5") (pintype "bidirectional"))
      (node (ref "U13") (pin "5") (pinfunction "DQ_5") (pintype "bidirectional"))
      (node (ref "U14") (pin "5") (pinfunction "DQ_5") (pintype "bidirectional"))
      (node (ref "U5") (pin "5") (pinfunction "DQ_5") (pintype "bidirectional"))
      (node (ref "U6") (pin "5") (pinfunction "DQ_5") (pintype "bidirectional"))
      (node (ref "U7") (pin "5") (pinfunction "DQ_5") (pintype "bidirectional"))
      (node (ref "U8") (pin "5") (pinfunction "DQ_5") (pintype "bidirectional"))
      (node (ref "U9") (pin "5") (pinfunction "DQ_5") (pintype "bidirectional"))
    )
    (net (code "3") (name "DATA2") (class "Default")
      (node (ref "J$1") (pin "7") (pinfunction "7_7") (pintype "passive"))
      (node (ref "R2") (pin "2") (pinfunction "22_2") (pintype "passive"))
      (node (ref "U15") (pin "5") (pinfunction "DQ_5") (pintype "bidirectional"))
      (node (ref "U16") (pin "5") (pinfunction "DQ_5") (pintype "bidirectional"))
      (node (ref "U17") (pin "5") (pinfunction "DQ_5") (pintype "bidirectional"))
      (node (ref "U18") (pin "5") (pinfunction "DQ_5") (pintype "bidirectional"))
      (node (ref "U19") (pin "5") (pinfunction "DQ_5") (pintype "bidirectional"))
      (node (ref "U20") (pin "5") (pinfunction "DQ_5") (pintype "bidirectional"))
      (node (ref "U21") (pin "5") (pinfunction "DQ_5") (pintype "bidirectional"))
      (node (ref "U22") (pin "5") (pinfunction "DQ_5") (pintype "bidirectional"))
      (node (ref "U23") (pin "5") (pinfunction "DQ_5") (pintype "bidirectional"))
      (node (ref "U24") (pin "5") (pinfunction "DQ_5") (pintype "bidirectional"))
    )
    (net (code "4") (name "DATA3") (class "Default")
      (node (ref "J$1") (pin "6") (pinfunction "6_6") (pintype "passive"))
      (node (ref "R3") (pin "2") (pinfunction "22_2") (pintype "passive"))
      (node (ref "U25") (pin "5") (pinfunction "DQ_5") (pintype "bidirectional"))
      (node (ref "U26") (pin "5") (pinfunction "DQ_5") (pintype "bidirectional"))
      (node (ref "U27") (pin "5") (pinfunction "DQ_5") (pintype "bidirectional"))
      (node (ref "U28") (pin "5") (pinfunction "DQ_5") (pintype "bidirectional"))
      (node (ref "U29") (pin "5") (pinfunction "DQ_5") (pintype "bidirectional"))
      (node (ref "U30") (pin "5") (pinfunction "DQ_5") (pintype "bidirectional"))
      (node (ref "U31") (pin "5") (pinfunction "DQ_5") (pintype "bidirectional"))
      (node (ref "U32") (pin "5") (pinfunction "DQ_5") (pintype "bidirectional"))
      (node (ref "U33") (pin "5") (pinfunction "DQ_5") (pintype "bidirectional"))
      (node (ref "U34") (pin "5") (pinfunction "DQ_5") (pintype "bidirectional"))
    )
    (net (code "5") (name "GND") (class "Default")
      (node (ref "J$1") (pin "10") (pinfunction "10_10") (pintype "passive"))
      (node (ref "J$1") (pin "11") (pinfunction "11_11") (pintype "passive"))
      (node (ref "J$1") (pin "9") (pinfunction "9_9") (pintype "passive"))
      (node (ref "U1") (pin "4") (pinfunction "GND_4") (pintype "passive"))
      (node (ref "U10") (pin "1") (pinfunction "GND_1") (pintype "power_in"))
      (node (ref "U10") (pin "8") (pinfunction "AD2_8") (pintype "input"))
      (node (ref "U10") (pin "9") (pinfunction "AD3_9") (pintype "input"))
      (node (ref "U10") (pin "THERMAL") (pinfunction "PAD_THERMAL") (pintype "passive"))
      (node (ref "U11") (pin "1") (pinfunction "GND_1") (pintype "power_in"))
      (node (ref "U11") (pin "7") (pinfunction "AD1_7") (pintype "input"))
      (node (ref "U11") (pin "9") (pinfunction "AD3_9") (pintype "input"))
      (node (ref "U11") (pin "THERMAL") (pinfunction "PAD_THERMAL") (pintype "passive"))
      (node (ref "U12") (pin "1") (pinfunction "GND_1") (pintype "power_in"))
      (node (ref "U12") (pin "7") (pinfunction "AD1_7") (pintype "input"))
      (node (ref "U12") (pin "8") (pinfunction "AD2_8") (pintype "input"))
      (node (ref "U12") (pin "THERMAL") (pinfunction "PAD_THERMAL") (pintype "passive"))
      (node (ref "U13") (pin "1") (pinfunction "GND_1") (pintype "power_in"))
      (node (ref "U13") (pin "6") (pinfunction "AD0_6") (pintype "input"))
      (node (ref "U13") (pin "9") (pinfunction "AD3_9") (pintype "input"))
      (node (ref "U13") (pin "THERMAL") (pinfunction "PAD_THERMAL") (pintype "passive"))
      (node (ref "U14") (pin "1") (pinfunction "GND_1") (pintype "power_in"))
      (node (ref "U14") (pin "6") (pinfunction "AD0_6") (pintype "input"))
      (node (ref "U14") (pin "7") (pinfunction "AD1_7") (pintype "input"))
      (node (ref "U14") (pin "THERMAL") (pinfunction "PAD_THERMAL") (pintype "passive"))
      (node (ref "U15") (pin "1") (pinfunction "GND_1") (pintype "power_in"))
      (node (ref "U15") (pin "6") (pinfunction "AD0_6") (pintype "input"))
      (node (ref "U15") (pin "7") (pinfunction "AD1_7") (pintype "input"))
      (node (ref "U15") (pin "8") (pinfunction "AD2_8") (pintype "input"))
      (node (ref "U15") (pin "9") (pinfunction "AD3_9") (pintype "input"))
      (node (ref "U15") (pin "THERMAL") (pinfunction "PAD_THERMAL") (pintype "passive"))
      (node (ref "U16") (pin "1") (pinfunction "GND_1") (pintype "power_in"))
      (node (ref "U16") (pin "7") (pinfunction "AD1_7") (pintype "input"))
      (node (ref "U16") (pin "8") (pinfunction "AD2_8") (pintype "input"))
      (node (ref "U16") (pin "9") (pinfunction "AD3_9") (pintype "input"))
      (node (ref "U16") (pin "THERMAL") (pinfunction "PAD_THERMAL") (pintype "passive"))
      (node (ref "U17") (pin "1") (pinfunction "GND_1") (pintype "power_in"))
      (node (ref "U17") (pin "6") (pinfunction "AD0_6") (pintype "input"))
      (node (ref "U17") (pin "8") (pinfunction "AD2_8") (pintype "input"))
      (node (ref "U17") (pin "9") (pinfunction "AD3_9") (pintype "input"))
      (node (ref "U17") (pin "THERMAL") (pinfunction "PAD_THERMAL") (pintype "passive"))
      (node (ref "U18") (pin "1") (pinfunction "GND_1") (pintype "power_in"))
      (node (ref "U18") (pin "6") (pinfunction "AD0_6") (pintype "input"))
      (node (ref "U18") (pin "7") (pinfunction "AD1_7") (pintype "input"))
      (node (ref "U18") (pin "9") (pinfunction "AD3_9") (pintype "input"))
      (node (ref "U18") (pin "THERMAL") (pinfunction "PAD_THERMAL") (pintype "passive"))
      (node (ref "U19") (pin "1") (pinfunction "GND_1") (pintype "power_in"))
      (node (ref "U19") (pin "6") (pinfunction "AD0_6") (pintype "input"))
      (node (ref "U19") (pin "7") (pinfunction "AD1_7") (pintype "input"))
      (node (ref "U19") (pin "8") (pinfunction "AD2_8") (pintype "input"))
      (node (ref "U19") (pin "THERMAL") (pinfunction "PAD_THERMAL") (pintype "passive"))
      (node (ref "U2") (pin "4") (pinfunction "GND_4") (pintype "passive"))
      (node (ref "U20") (pin "1") (pinfunction "GND_1") (pintype "power_in"))
      (node (ref "U20") (pin "8") (pinfunction "AD2_8") (pintype "input"))
      (node (ref "U20") (pin "9") (pinfunction "AD3_9") (pintype "input"))
      (node (ref "U20") (pin "THERMAL") (pinfunction "PAD_THERMAL") (pintype "passive"))
      (node (ref "U21") (pin "1") (pinfunction "GND_1") (pintype "power_in"))
      (node (ref "U21") (pin "7") (pinfunction "AD1_7") (pintype "input"))
      (node (ref "U21") (pin "9") (pinfunction "AD3_9") (pintype "input"))
      (node (ref "U21") (pin "THERMAL") (pinfunction "PAD_THERMAL") (pintype "passive"))
      (node (ref "U22") (pin "1") (pinfunction "GND_1") (pintype "power_in"))
      (node (ref "U22") (pin "7") (pinfunction "AD1_7") (pintype "input"))
      (node (ref "U22") (pin "8") (pinfunction "AD2_8") (pintype "input"))
      (node (ref "U22") (pin "THERMAL") (pinfunction "PAD_THERMAL") (pintype "passive"))
      (node (ref "U23") (pin "1") (pinfunction "GND_1") (pintype "power_in"))
      (node (ref "U23") (pin "6") (pinfunction "AD0_6") (pintype "input"))
      (node (ref "U23") (pin "9") (pinfunction "AD3_9") (pintype "input"))
      (node (ref "U23") (pin "THERMAL") (pinfunction "PAD_THERMAL") (pintype "passive"))
      (node (ref "U24") (pin "1") (pinfunction "GND_1") (pintype "power_in"))
      (node (ref "U24") (pin "6") (pinfunction "AD0_6") (pintype "input"))
      (node (ref "U24") (pin "7") (pinfunction "AD1_7") (pintype "input"))
      (node (ref "U24") (pin "THERMAL") (pinfunction "PAD_THERMAL") (pintype "passive"))
      (node (ref "U25") (pin "1") (pinfunction "GND_1") (pintype "power_in"))
      (node (ref "U25") (pin "6") (pinfunction "AD0_6") (pintype "input"))
      (node (ref "U25") (pin "7") (pinfunction "AD1_7") (pintype "input"))
      (node (ref "U25") (pin "8") (pinfunction "AD2_8") (pintype "input"))
      (node (ref "U25") (pin "9") (pinfunction "AD3_9") (pintype "input"))
      (node (ref "U25") (pin "THERMAL") (pinfunction "PAD_THERMAL") (pintype "passive"))
      (node (ref "U26") (pin "1") (pinfunction "GND_1") (pintype "power_in"))
      (node (ref "U26") (pin "7") (pinfunction "AD1_7") (pintype "input"))
      (node (ref "U26") (pin "8") (pinfunction "AD2_8") (pintype "input"))
      (node (ref "U26") (pin "9") (pinfunction "AD3_9") (pintype "input"))
      (node (ref "U26") (pin "THERMAL") (pinfunction "PAD_THERMAL") (pintype "passive"))
      (node (ref "U27") (pin "1") (pinfunction "GND_1") (pintype "power_in"))
      (node (ref "U27") (pin "6") (pinfunction "AD0_6") (pintype "input"))
      (node (ref "U27") (pin "8") (pinfunction "AD2_8") (pintype "input"))
      (node (ref "U27") (pin "9") (pinfunction "AD3_9") (pintype "input"))
      (node (ref "U27") (pin "THERMAL") (pinfunction "PAD_THERMAL") (pintype "passive"))
      (node (ref "U28") (pin "1") (pinfunction "GND_1") (pintype "power_in"))
      (node (ref "U28") (pin "6") (pinfunction "AD0_6") (pintype "input"))
      (node (ref "U28") (pin "7") (pinfunction "AD1_7") (pintype "input"))
      (node (ref "U28") (pin "9") (pinfunction "AD3_9") (pintype "input"))
      (node (ref "U28") (pin "THERMAL") (pinfunction "PAD_THERMAL") (pintype "passive"))
      (node (ref "U29") (pin "1") (pinfunction "GND_1") (pintype "power_in"))
      (node (ref "U29") (pin "6") (pinfunction "AD0_6") (pintype "input"))
      (node (ref "U29") (pin "7") (pinfunction "AD1_7") (pintype "input"))
      (node (ref "U29") (pin "8") (pinfunction "AD2_8") (pintype "input"))
      (node (ref "U29") (pin "THERMAL") (pinfunction "PAD_THERMAL") (pintype "passive"))
      (node (ref "U3") (pin "4") (pinfunction "GND_4") (pintype "passive"))
      (node (ref "U30") (pin "1") (pinfunction "GND_1") (pintype "power_in"))
      (node (ref "U30") (pin "8") (pinfunction "AD2_8") (pintype "input"))
      (node (ref "U30") (pin "9") (pinfunction "AD3_9") (pintype "input"))
      (node (ref "U30") (pin "THERMAL") (pinfunction "PAD_THERMAL") (pintype "passive"))
      (node (ref "U31") (pin "1") (pinfunction "GND_1") (pintype "power_in"))
      (node (ref "U31") (pin "7") (pinfunction "AD1_7") (pintype "input"))
      (node (ref "U31") (pin "9") (pinfunction "AD3_9") (pintype "input"))
      (node (ref "U31") (pin "THERMAL") (pinfunction "PAD_THERMAL") (pintype "passive"))
      (node (ref "U32") (pin "1") (pinfunction "GND_1") (pintype "power_in"))
      (node (ref "U32") (pin "7") (pinfunction "AD1_7") (pintype "input"))
      (node (ref "U32") (pin "8") (pinfunction "AD2_8") (pintype "input"))
      (node (ref "U32") (pin "THERMAL") (pinfunction "PAD_THERMAL") (pintype "passive"))
      (node (ref "U33") (pin "1") (pinfunction "GND_1") (pintype "power_in"))
      (node (ref "U33") (pin "6") (pinfunction "AD0_6") (pintype "input"))
      (node (ref "U33") (pin "9") (pinfunction "AD3_9") (pintype "input"))
      (node (ref "U33") (pin "THERMAL") (pinfunction "PAD_THERMAL") (pintype "passive"))
      (node (ref "U34") (pin "1") (pinfunction "GND_1") (pintype "power_in"))
      (node (ref "U34") (pin "6") (pinfunction "AD0_6") (pintype "input"))
      (node (ref "U34") (pin "7") (pinfunction "AD1_7") (pintype "input"))
      (node (ref "U34") (pin "THERMAL") (pinfunction "PAD_THERMAL") (pintype "passive"))
      (node (ref "U4") (pin "4") (pinfunction "GND_4") (pintype "passive"))
      (node (ref "U5") (pin "1") (pinfunction "GND_1") (pintype "power_in"))
      (node (ref "U5") (pin "6") (pinfunction "AD0_6") (pintype "input"))
      (node (ref "U5") (pin "7") (pinfunction "AD1_7") (pintype "input"))
      (node (ref "U5") (pin "8") (pinfunction "AD2_8") (pintype "input"))
      (node (ref "U5") (pin "9") (pinfunction "AD3_9") (pintype "input"))
      (node (ref "U5") (pin "THERMAL") (pinfunction "PAD_THERMAL") (pintype "passive"))
      (node (ref "U6") (pin "1") (pinfunction "GND_1") (pintype "power_in"))
      (node (ref "U6") (pin "7") (pinfunction "AD1_7") (pintype "input"))
      (node (ref "U6") (pin "8") (pinfunction "AD2_8") (pintype "input"))
      (node (ref "U6") (pin "9") (pinfunction "AD3_9") (pintype "input"))
      (node (ref "U6") (pin "THERMAL") (pinfunction "PAD_THERMAL") (pintype "passive"))
      (node (ref "U7") (pin "1") (pinfunction "GND_1") (pintype "power_in"))
      (node (ref "U7") (pin "6") (pinfunction "AD0_6") (pintype "input"))
      (node (ref "U7") (pin "8") (pinfunction "AD2_8") (pintype "input"))
      (node (ref "U7") (pin "9") (pinfunction "AD3_9") (pintype "input"))
      (node (ref "U7") (pin "THERMAL") (pinfunction "PAD_THERMAL") (pintype "passive"))
      (node (ref "U8") (pin "1") (pinfunction "GND_1") (pintype "power_in"))
      (node (ref "U8") (pin "6") (pinfunction "AD0_6") (pintype "input"))
      (node (ref "U8") (pin "7") (pinfunction "AD1_7") (pintype "input"))
      (node (ref "U8") (pin "9") (pinfunction "AD3_9") (pintype "input"))
      (node (ref "U8") (pin "THERMAL") (pinfunction "PAD_THERMAL") (pintype "passive"))
      (node (ref "U9") (pin "1") (pinfunction "GND_1") (pintype "power_in"))
      (node (ref "U9") (pin "6") (pinfunction "AD0_6") (pintype "input"))
      (node (ref "U9") (pin "7") (pinfunction "AD1_7") (pintype "input"))
      (node (ref "U9") (pin "8") (pinfunction "AD2_8") (pintype "input"))
      (node (ref "U9") (pin "THERMAL") (pinfunction "PAD_THERMAL") (pintype "passive"))
    )
    (net (code "6") (name "Net-(U5-T+)") (class "Default")
      (node (ref "L1") (pin "1") (pinfunction "1_1") (pintype "passive"))
      (node (ref "U5") (pin "3") (pinfunction "T+_3") (pintype "input"))
    )
    (net (code "7") (name "Net-(U5-T-)") (class "Default")
      (node (ref "L2") (pin "1") (pinfunction "1_1") (pintype "passive"))
      (node (ref "U5") (pin "2") (pinfunction "T-_2") (pintype "input"))
    )
    (net (code "8") (name "Net-(U6-T+)") (class "Default")
      (node (ref "L3") (pin "1") (pinfunction "1_1") (pintype "passive"))
      (node (ref "U6") (pin "3") (pinfunction "T+_3") (pintype "input"))
    )
    (net (code "9") (name "Net-(U6-T-)") (class "Default")
      (node (ref "L4") (pin "1") (pinfunction "1_1") (pintype "passive"))
      (node (ref "U6") (pin "2") (pinfunction "T-_2") (pintype "input"))
    )
    (net (code "10") (name "Net-(U7-T+)") (class "Default")
      (node (ref "L5") (pin "1") (pinfunction "1_1") (pintype "passive"))
      (node (ref "U7") (pin "3") (pinfunction "T+_3") (pintype "input"))
    )
    (net (code "11") (name "Net-(U7-T-)") (class "Default")
      (node (ref "L6") (pin "1") (pinfunction "1_1") (pintype "passive"))
      (node (ref "U7") (pin "2") (pinfunction "T-_2") (pintype "input"))
    )
    (net (code "12") (name "Net-(U8-T+)") (class "Default")
      (node (ref "L7") (pin "1") (pinfunction "1_1") (pintype "passive"))
      (node (ref "U8") (pin "3") (pinfunction "T+_3") (pintype "input"))
    )
    (net (code "13") (name "Net-(U8-T-)") (class "Default")
      (node (ref "L8") (pin "1") (pinfunction "1_1") (pintype "passive"))
      (node (ref "U8") (pin "2") (pinfunction "T-_2") (pintype "input"))
    )
    (net (code "14") (name "Net-(U9-T+)") (class "Default")
      (node (ref "L9") (pin "1") (pinfunction "1_1") (pintype "passive"))
      (node (ref "U9") (pin "3") (pinfunction "T+_3") (pintype "input"))
    )
    (net (code "15") (name "Net-(U9-T-)") (class "Default")
      (node (ref "L10") (pin "1") (pinfunction "1_1") (pintype "passive"))
      (node (ref "U9") (pin "2") (pinfunction "T-_2") (pintype "input"))
    )
    (net (code "16") (name "Net-(U10-T+)") (class "Default")
      (node (ref "L11") (pin "1") (pinfunction "1_1") (pintype "passive"))
      (node (ref "U10") (pin "3") (pinfunction "T+_3") (pintype "input"))
    )
    (net (code "17") (name "Net-(U10-T-)") (class "Default")
      (node (ref "L12") (pin "1") (pinfunction "1_1") (pintype "passive"))
      (node (ref "U10") (pin "2") (pinfunction "T-_2") (pintype "input"))
    )
    (net (code "18") (name "Net-(U11-T+)") (class "Default")
      (node (ref "L13") (pin "1") (pinfunction "1_1") (pintype "passive"))
      (node (ref "U11") (pin "3") (pinfunction "T+_3") (pintype "input"))
    )
    (net (code "19") (name "Net-(U11-T-)") (class "Default")
      (node (ref "L14") (pin "1") (pinfunction "1_1") (pintype "passive"))
      (node (ref "U11") (pin "2") (pinfunction "T-_2") (pintype "input"))
    )
    (net (code "20") (name "Net-(U12-T+)") (class "Default")
      (node (ref "L15") (pin "1") (pinfunction "1_1") (pintype "passive"))
      (node (ref "U12") (pin "3") (pinfunction "T+_3") (pintype "input"))
    )
    (net (code "21") (name "Net-(U12-T-)") (class "Default")
      (node (ref "L16") (pin "1") (pinfunction "1_1") (pintype "passive"))
      (node (ref "U12") (pin "2") (pinfunction "T-_2") (pintype "input"))
    )
    (net (code "22") (name "Net-(U13-T+)") (class "Default")
      (node (ref "L17") (pin "1") (pinfunction "1_1") (pintype "passive"))
      (node (ref "U13") (pin "3") (pinfunction "T+_3") (pintype "input"))
    )
    (net (code "23") (name "Net-(U13-T-)") (class "Default")
      (node (ref "L18") (pin "1") (pinfunction "1_1") (pintype "passive"))
      (node (ref "U13") (pin "2") (pinfunction "T-_2") (pintype "input"))
    )
    (net (code "24") (name "Net-(U14-T+)") (class "Default")
      (node (ref "L19") (pin "1") (pinfunction "1_1") (pintype "passive"))
      (node (ref "U14") (pin "3") (pinfunction "T+_3") (pintype "input"))
    )
    (net (code "25") (name "Net-(U14-T-)") (class "Default")
      (node (ref "L20") (pin "1") (pinfunction "1_1") (pintype "passive"))
      (node (ref "U14") (pin "2") (pinfunction "T-_2") (pintype "input"))
    )
    (net (code "26") (name "Net-(U15-T+)") (class "Default")
      (node (ref "L21") (pin "1") (pinfunction "1_1") (pintype "passive"))
      (node (ref "U15") (pin "3") (pinfunction "T+_3") (pintype "input"))
    )
    (net (code "27") (name "Net-(U15-T-)") (class "Default")
      (node (ref "L22") (pin "1") (pinfunction "1_1") (pintype "passive"))
      (node (ref "U15") (pin "2") (pinfunction "T-_2") (pintype "input"))
    )
    (net (code "28") (name "Net-(U16-T+)") (class "Default")
      (node (ref "L23") (pin "1") (pinfunction "1_1") (pintype "passive"))
      (node (ref "U16") (pin "3") (pinfunction "T+_3") (pintype "input"))
    )
    (net (code "29") (name "Net-(U16-T-)") (class "Default")
      (node (ref "L24") (pin "1") (pinfunction "1_1") (pintype "passive"))
      (node (ref "U16") (pin "2") (pinfunction "T-_2") (pintype "input"))
    )
    (net (code "30") (name "Net-(U17-T+)") (class "Default")
      (node (ref "L25") (pin "1") (pinfunction "1_1") (pintype "passive"))
      (node (ref "U17") (pin "3") (pinfunction "T+_3") (pintype "input"))
    )
    (net (code "31") (name "Net-(U17-T-)") (class "Default")
      (node (ref "L26") (pin "1") (pinfunction "1_1") (pintype "passive"))
      (node (ref "U17") (pin "2") (pinfunction "T-_2") (pintype "input"))
    )
    (net (code "32") (name "Net-(U18-T+)") (class "Default")
      (node (ref "L27") (pin "1") (pinfunction "1_1") (pintype "passive"))
      (node (ref "U18") (pin "3") (pinfunction "T+_3") (pintype "input"))
    )
    (net (code "33") (name "Net-(U18-T-)") (class "Default")
      (node (ref "L28") (pin "1") (pinfunction "1_1") (pintype "passive"))
      (node (ref "U18") (pin "2") (pinfunction "T-_2") (pintype "input"))
    )
    (net (code "34") (name "Net-(U19-T+)") (class "Default")
      (node (ref "L29") (pin "1") (pinfunction "1_1") (pintype "passive"))
      (node (ref "U19") (pin "3") (pinfunction "T+_3") (pintype "input"))
    )
    (net (code "35") (name "Net-(U19-T-)") (class "Default")
      (node (ref "L30") (pin "1") (pinfunction "1_1") (pintype "passive"))
      (node (ref "U19") (pin "2") (pinfunction "T-_2") (pintype "input"))
    )
    (net (code "36") (name "Net-(U20-T+)") (class "Default")
      (node (ref "L31") (pin "1") (pinfunction "1_1") (pintype "passive"))
      (node (ref "U20") (pin "3") (pinfunction "T+_3") (pintype "input"))
    )
    (net (code "37") (name "Net-(U20-T-)") (class "Default")
      (node (ref "L32") (pin "1") (pinfunction "1_1") (pintype "passive"))
      (node (ref "U20") (pin "2") (pinfunction "T-_2") (pintype "input"))
    )
    (net (code "38") (name "Net-(U21-T+)") (class "Default")
      (node (ref "L33") (pin "1") (pinfunction "1_1") (pintype "passive"))
      (node (ref "U21") (pin "3") (pinfunction "T+_3") (pintype "input"))
    )
    (net (code "39") (name "Net-(U21-T-)") (class "Default")
      (node (ref "L34") (pin "1") (pinfunction "1_1") (pintype "passive"))
      (node (ref "U21") (pin "2") (pinfunction "T-_2") (pintype "input"))
    )
    (net (code "40") (name "Net-(U22-T+)") (class "Default")
      (node (ref "L35") (pin "1") (pinfunction "1_1") (pintype "passive"))
      (node (ref "U22") (pin "3") (pinfunction "T+_3") (pintype "input"))
    )
    (net (code "41") (name "Net-(U22-T-)") (class "Default")
      (node (ref "L36") (pin "1") (pinfunction "1_1") (pintype "passive"))
      (node (ref "U22") (pin "2") (pinfunction "T-_2") (pintype "input"))
    )
    (net (code "42") (name "Net-(U23-T+)") (class "Default")
      (node (ref "L37") (pin "1") (pinfunction "1_1") (pintype "passive"))
      (node (ref "U23") (pin "3") (pinfunction "T+_3") (pintype "input"))
    )
    (net (code "43") (name "Net-(U23-T-)") (class "Default")
      (node (ref "L38") (pin "1") (pinfunction "1_1") (pintype "passive"))
      (node (ref "U23") (pin "2") (pinfunction "T-_2") (pintype "input"))
    )
    (net (code "44") (name "Net-(U24-T+)") (class "Default")
      (node (ref "L39") (pin "1") (pinfunction "1_1") (pintype "passive"))
      (node (ref "U24") (pin "3") (pinfunction "T+_3") (pintype "input"))
    )
    (net (code "45") (name "Net-(U24-T-)") (class "Default")
      (node (ref "L40") (pin "1") (pinfunction "1_1") (pintype "passive"))
      (node (ref "U24") (pin "2") (pinfunction "T-_2") (pintype "input"))
    )
    (net (code "46") (name "Net-(U25-T+)") (class "Default")
      (node (ref "L41") (pin "1") (pinfunction "1_1") (pintype "passive"))
      (node (ref "U25") (pin "3") (pinfunction "T+_3") (pintype "input"))
    )
    (net (code "47") (name "Net-(U25-T-)") (class "Default")
      (node (ref "L42") (pin "1") (pinfunction "1_1") (pintype "passive"))
      (node (ref "U25") (pin "2") (pinfunction "T-_2") (pintype "input"))
    )
    (net (code "48") (name "Net-(U26-T+)") (class "Default")
      (node (ref "L43") (pin "1") (pinfunction "1_1") (pintype "passive"))
      (node (ref "U26") (pin "3") (pinfunction "T+_3") (pintype "input"))
    )
    (net (code "49") (name "Net-(U26-T-)") (class "Default")
      (node (ref "L44") (pin "1") (pinfunction "1_1") (pintype "passive"))
      (node (ref "U26") (pin "2") (pinfunction "T-_2") (pintype "input"))
    )
    (net (code "50") (name "Net-(U27-T+)") (class "Default")
      (node (ref "L45") (pin "1") (pinfunction "1_1") (pintype "passive"))
      (node (ref "U27") (pin "3") (pinfunction "T+_3") (pintype "input"))
    )
    (net (code "51") (name "Net-(U27-T-)") (class "Default")
      (node (ref "L46") (pin "1") (pinfunction "1_1") (pintype "passive"))
      (node (ref "U27") (pin "2") (pinfunction "T-_2") (pintype "input"))
    )
    (net (code "52") (name "Net-(U28-T+)") (class "Default")
      (node (ref "L47") (pin "1") (pinfunction "1_1") (pintype "passive"))
      (node (ref "U28") (pin "3") (pinfunction "T+_3") (pintype "input"))
    )
    (net (code "53") (name "Net-(U28-T-)") (class "Default")
      (node (ref "L48") (pin "1") (pinfunction "1_1") (pintype "passive"))
      (node (ref "U28") (pin "2") (pinfunction "T-_2") (pintype "input"))
    )
    (net (code "54") (name "Net-(U29-T+)") (class "Default")
      (node (ref "L49") (pin "1") (pinfunction "1_1") (pintype "passive"))
      (node (ref "U29") (pin "3") (pinfunction "T+_3") (pintype "input"))
    )
    (net (code "55") (name "Net-(U29-T-)") (class "Default")
      (node (ref "L50") (pin "1") (pinfunction "1_1") (pintype "passive"))
      (node (ref "U29") (pin "2") (pinfunction "T-_2") (pintype "input"))
    )
    (net (code "56") (name "Net-(U30-T+)") (class "Default")
      (node (ref "L51") (pin "1") (pinfunction "1_1") (pintype "passive"))
      (node (ref "U30") (pin "3") (pinfunction "T+_3") (pintype "input"))
    )
    (net (code "57") (name "Net-(U30-T-)") (class "Default")
      (node (ref "L52") (pin "1") (pinfunction "1_1") (pintype "passive"))
      (node (ref "U30") (pin "2") (pinfunction "T-_2") (pintype "input"))
    )
    (net (code "58") (name "Net-(U31-T+)") (class "Default")
      (node (ref "L53") (pin "1") (pinfunction "1_1") (pintype "passive"))
      (node (ref "U31") (pin "3") (pinfunction "T+_3") (pintype "input"))
    )
    (net (code "59") (name "Net-(U31-T-)") (class "Default")
      (node (ref "L54") (pin "1") (pinfunction "1_1") (pintype "passive"))
      (node (ref "U31") (pin "2") (pinfunction "T-_2") (pintype "input"))
    )
    (net (code "60") (name "Net-(U32-T+)") (class "Default")
      (node (ref "L55") (pin "1") (pinfunction "1_1") (pintype "passive"))
      (node (ref "U32") (pin "3") (pinfunction "T+_3") (pintype "input"))
    )
    (net (code "61") (name "Net-(U32-T-)") (class "Default")
      (node (ref "L56") (pin "1") (pinfunction "1_1") (pintype "passive"))
      (node (ref "U32") (pin "2") (pinfunction "T-_2") (pintype "input"))
    )
    (net (code "62") (name "Net-(U33-T+)") (class "Default")
      (node (ref "L57") (pin "1") (pinfunction "1_1") (pintype "passive"))
      (node (ref "U33") (pin "3") (pinfunction "T+_3") (pintype "input"))
    )
    (net (code "63") (name "Net-(U33-T-)") (class "Default")
      (node (ref "L58") (pin "1") (pinfunction "1_1") (pintype "passive"))
      (node (ref "U33") (pin "2") (pinfunction "T-_2") (pintype "input"))
    )
    (net (code "64") (name "Net-(U34-T+)") (class "Default")
      (node (ref "L59") (pin "1") (pinfunction "1_1") (pintype "passive"))
      (node (ref "U34") (pin "3") (pinfunction "T+_3") (pintype "input"))
    )
    (net (code "65") (name "Net-(U34-T-)") (class "Default")
      (node (ref "L60") (pin "1") (pinfunction "1_1") (pintype "passive"))
      (node (ref "U34") (pin "2") (pinfunction "T-_2") (pintype "input"))
    )
    (net (code "66") (name "T1+") (class "Default")
      (node (ref "J$2") (pin "12") (pinfunction "12_12") (pintype "passive"))
      (node (ref "L1") (pin "2") (pinfunction "2_2") (pintype "passive"))
    )
    (net (code "67") (name "T1-") (class "Default")
      (node (ref "J$2") (pin "11") (pinfunction "11_11") (pintype "passive"))
      (node (ref "L2") (pin "2") (pinfunction "2_2") (pintype "passive"))
    )
    (net (code "68") (name "T2+") (class "Default")
      (node (ref "J$2") (pin "10") (pinfunction "10_10") (pintype "passive"))
      (node (ref "L3") (pin "2") (pinfunction "2_2") (pintype "passive"))
    )
    (net (code "69") (name "T2-") (class "Default")
      (node (ref "J$2") (pin "9") (pinfunction "9_9") (pintype "passive"))
      (node (ref "L4") (pin "2") (pinfunction "2_2") (pintype "passive"))
    )
    (net (code "70") (name "T3+") (class "Default")
      (node (ref "J$2") (pin "8") (pinfunction "8_8") (pintype "passive"))
      (node (ref "L5") (pin "2") (pinfunction "2_2") (pintype "passive"))
    )
    (net (code "71") (name "T3-") (class "Default")
      (node (ref "J$2") (pin "7") (pinfunction "7_7") (pintype "passive"))
      (node (ref "L6") (pin "2") (pinfunction "2_2") (pintype "passive"))
    )
    (net (code "72") (name "T4+") (class "Default")
      (node (ref "J$2") (pin "6") (pinfunction "6_6") (pintype "passive"))
      (node (ref "L7") (pin "2") (pinfunction "2_2") (pintype "passive"))
    )
    (net (code "73") (name "T4-") (class "Default")
      (node (ref "J$2") (pin "5") (pinfunction "5_5") (pintype "passive"))
      (node (ref "L8") (pin "2") (pinfunction "2_2") (pintype "passive"))
    )
    (net (code "74") (name "T5+") (class "Default")
      (node (ref "J$2") (pin "4") (pinfunction "4_4") (pintype "passive"))
      (node (ref "L9") (pin "2") (pinfunction "2_2") (pintype "passive"))
    )
    (net (code "75") (name "T5-") (class "Default")
      (node (ref "J$2") (pin "3") (pinfunction "3_3") (pintype "passive"))
      (node (ref "L10") (pin "2") (pinfunction "2_2") (pintype "passive"))
    )
    (net (code "76") (name "T6+") (class "Default")
      (node (ref "J$2") (pin "2") (pinfunction "2_2") (pintype "passive"))
      (node (ref "L11") (pin "2") (pinfunction "2_2") (pintype "passive"))
    )
    (net (code "77") (name "T6-") (class "Default")
      (node (ref "J$2") (pin "1") (pinfunction "1_1") (pintype "passive"))
      (node (ref "L12") (pin "2") (pinfunction "2_2") (pintype "passive"))
    )
    (net (code "78") (name "T7+") (class "Default")
      (node (ref "J$3") (pin "12") (pinfunction "12_12") (pintype "passive"))
      (node (ref "L13") (pin "2") (pinfunction "2_2") (pintype "passive"))
    )
    (net (code "79") (name "T7-") (class "Default")
      (node (ref "J$3") (pin "11") (pinfunction "11_11") (pintype "passive"))
      (node (ref "L14") (pin "2") (pinfunction "2_2") (pintype "passive"))
    )
    (net (code "80") (name "T8+") (class "Default")
      (node (ref "J$3") (pin "10") (pinfunction "10_10") (pintype "passive"))
      (node (ref "L15") (pin "2") (pinfunction "2_2") (pintype "passive"))
    )
    (net (code "81") (name "T8-") (class "Default")
      (node (ref "J$3") (pin "9") (pinfunction "9_9") (pintype "passive"))
      (node (ref "L16") (pin "2") (pinfunction "2_2") (pintype "passive"))
    )
    (net (code "82") (name "T9+") (class "Default")
      (node (ref "J$3") (pin "8") (pinfunction "8_8") (pintype "passive"))
      (node (ref "L17") (pin "2") (pinfunction "2_2") (pintype "passive"))
    )
    (net (code "83") (name "T9-") (class "Default")
      (node (ref "J$3") (pin "7") (pinfunction "7_7") (pintype "passive"))
      (node (ref "L18") (pin "2") (pinfunction "2_2") (pintype "passive"))
    )
    (net (code "84") (name "T10+") (class "Default")
      (node (ref "J$3") (pin "6") (pinfunction "6_6") (pintype "passive"))
      (node (ref "L19") (pin "2") (pinfunction "2_2") (pintype "passive"))
    )
    (net (code "85") (name "T10-") (class "Default")
      (node (ref "J$3") (pin "5") (pinfunction "5_5") (pintype "passive"))
      (node (ref "L20") (pin "2") (pinfunction "2_2") (pintype "passive"))
    )
    (net (code "86") (name "T11+") (class "Default")
      (node (ref "J$3") (pin "4") (pinfunction "4_4") (pintype "passive"))
      (node (ref "L21") (pin "2") (pinfunction "2_2") (pintype "passive"))
    )
    (net (code "87") (name "T11-") (class "Default")
      (node (ref "J$3") (pin "3") (pinfunction "3_3") (pintype "passive"))
      (node (ref "L22") (pin "2") (pinfunction "2_2") (pintype "passive"))
    )
    (net (code "88") (name "T12+") (class "Default")
      (node (ref "J$3") (pin "2") (pinfunction "2_2") (pintype "passive"))
      (node (ref "L23") (pin "2") (pinfunction "2_2") (pintype "passive"))
    )
    (net (code "89") (name "T12-") (class "Default")
      (node (ref "J$3") (pin "1") (pinfunction "1_1") (pintype "passive"))
      (node (ref "L24") (pin "2") (pinfunction "2_2") (pintype "passive"))
    )
    (net (code "90") (name "T13+") (class "Default")
      (node (ref "J$4") (pin "12") (pinfunction "12_12") (pintype "passive"))
      (node (ref "L25") (pin "2") (pinfunction "2_2") (pintype "passive"))
    )
    (net (code "91") (name "T13-") (class "Default")
      (node (ref "J$4") (pin "11") (pinfunction "11_11") (pintype "passive"))
      (node (ref "L26") (pin "2") (pinfunction "2_2") (pintype "passive"))
    )
    (net (code "92") (name "T14+") (class "Default")
      (node (ref "J$4") (pin "10") (pinfunction "10_10") (pintype "passive"))
      (node (ref "L27") (pin "2") (pinfunction "2_2") (pintype "passive"))
    )
    (net (code "93") (name "T14-") (class "Default")
      (node (ref "J$4") (pin "9") (pinfunction "9_9") (pintype "passive"))
      (node (ref "L28") (pin "2") (pinfunction "2_2") (pintype "passive"))
    )
    (net (code "94") (name "T15+") (class "Default")
      (node (ref "J$4") (pin "8") (pinfunction "8_8") (pintype "passive"))
      (node (ref "L29") (pin "2") (pinfunction "2_2") (pintype "passive"))
    )
    (net (code "95") (name "T15-") (class "Default")
      (node (ref "J$4") (pin "7") (pinfunction "7_7") (pintype "passive"))
      (node (ref "L30") (pin "2") (pinfunction "2_2") (pintype "passive"))
    )
    (net (code "96") (name "T16+") (class "Default")
      (node (ref "J$4") (pin "6") (pinfunction "6_6") (pintype "passive"))
      (node (ref "L31") (pin "2") (pinfunction "2_2") (pintype "passive"))
    )
    (net (code "97") (name "T16-") (class "Default")
      (node (ref "J$4") (pin "5") (pinfunction "5_5") (pintype "passive"))
      (node (ref "L32") (pin "2") (pinfunction "2_2") (pintype "passive"))
    )
    (net (code "98") (name "T17+") (class "Default")
      (node (ref "J$4") (pin "4") (pinfunction "4_4") (pintype "passive"))
      (node (ref "L33") (pin "2") (pinfunction "2_2") (pintype "passive"))
    )
    (net (code "99") (name "T17-") (class "Default")
      (node (ref "J$4") (pin "3") (pinfunction "3_3") (pintype "passive"))
      (node (ref "L34") (pin "2") (pinfunction "2_2") (pintype "passive"))
    )
    (net (code "100") (name "T18+") (class "Default")
      (node (ref "J$4") (pin "2") (pinfunction "2_2") (pintype "passive"))
      (node (ref "L35") (pin "2") (pinfunction "2_2") (pintype "passive"))
    )
    (net (code "101") (name "T18-") (class "Default")
      (node (ref "J$4") (pin "1") (pinfunction "1_1") (pintype "passive"))
      (node (ref "L36") (pin "2") (pinfunction "2_2") (pintype "passive"))
    )
    (net (code "102") (name "T19+") (class "Default")
      (node (ref "J$5") (pin "12") (pinfunction "12_12") (pintype "passive"))
      (node (ref "L37") (pin "2") (pinfunction "2_2") (pintype "passive"))
    )
    (net (code "103") (name "T19-") (class "Default")
      (node (ref "J$5") (pin "11") (pinfunction "11_11") (pintype "passive"))
      (node (ref "L38") (pin "2") (pinfunction "2_2") (pintype "passive"))
    )
    (net (code "104") (name "T20+") (class "Default")
      (node (ref "J$5") (pin "10") (pinfunction "10_10") (pintype "passive"))
      (node (ref "L39") (pin "2") (pinfunction "2_2") (pintype "passive"))
    )
    (net (code "105") (name "T20-") (class "Default")
      (node (ref "J$5") (pin "9") (pinfunction "9_9") (pintype "passive"))
      (node (ref "L40") (pin "2") (pinfunction "2_2") (pintype "passive"))
    )
    (net (code "106") (name "T21+") (class "Default")
      (node (ref "J$5") (pin "8") (pinfunction "8_8") (pintype "passive"))
      (node (ref "L41") (pin "2") (pinfunction "2_2") (pintype "passive"))
    )
    (net (code "107") (name "T21-") (class "Default")
      (node (ref "J$5") (pin "7") (pinfunction "7_7") (pintype "passive"))
      (node (ref "L42") (pin "2") (pinfunction "2_2") (pintype "passive"))
    )
    (net (code "108") (name "T22+") (class "Default")
      (node (ref "J$5") (pin "6") (pinfunction "6_6") (pintype "passive"))
      (node (ref "L43") (pin "2") (pinfunction "2_2") (pintype "passive"))
    )
    (net (code "109") (name "T22-") (class "Default")
      (node (ref "J$5") (pin "5") (pinfunction "5_5") (pintype "passive"))
      (node (ref "L44") (pin "2") (pinfunction "2_2") (pintype "passive"))
    )
    (net (code "110") (name "T23+") (class "Default")
      (node (ref "J$5") (pin "4") (pinfunction "4_4") (pintype "passive"))
      (node (ref "L45") (pin "2") (pinfunction "2_2") (pintype "passive"))
    )
    (net (code "111") (name "T23-") (class "Default")
      (node (ref "J$5") (pin "3") (pinfunction "3_3") (pintype "passive"))
      (node (ref "L46") (pin "2") (pinfunction "2_2") (pintype "passive"))
    )
    (net (code "112") (name "T24+") (class "Default")
      (node (ref "J$5") (pin "2") (pinfunction "2_2") (pintype "passive"))
      (node (ref "L47") (pin "2") (pinfunction "2_2") (pintype "passive"))
    )
    (net (code "113") (name "T24-") (class "Default")
      (node (ref "J$5") (pin "1") (pinfunction "1_1") (pintype "passive"))
      (node (ref "L48") (pin "2") (pinfunction "2_2") (pintype "passive"))
    )
    (net (code "114") (name "T25+") (class "Default")
      (node (ref "J$6") (pin "12") (pinfunction "12_12") (pintype "passive"))
      (node (ref "L49") (pin "2") (pinfunction "2_2") (pintype "passive"))
    )
    (net (code "115") (name "T25-") (class "Default")
      (node (ref "J$6") (pin "11") (pinfunction "11_11") (pintype "passive"))
      (node (ref "L50") (pin "2") (pinfunction "2_2") (pintype "passive"))
    )
    (net (code "116") (name "T26+") (class "Default")
      (node (ref "J$6") (pin "10") (pinfunction "10_10") (pintype "passive"))
      (node (ref "L51") (pin "2") (pinfunction "2_2") (pintype "passive"))
    )
    (net (code "117") (name "T26-") (class "Default")
      (node (ref "J$6") (pin "9") (pinfunction "9_9") (pintype "passive"))
      (node (ref "L52") (pin "2") (pinfunction "2_2") (pintype "passive"))
    )
    (net (code "118") (name "T27+") (class "Default")
      (node (ref "J$6") (pin "8") (pinfunction "8_8") (pintype "passive"))
      (node (ref "L53") (pin "2") (pinfunction "2_2") (pintype "passive"))
    )
    (net (code "119") (name "T27-") (class "Default")
      (node (ref "J$6") (pin "7") (pinfunction "7_7") (pintype "passive"))
      (node (ref "L54") (pin "2") (pinfunction "2_2") (pintype "passive"))
    )
    (net (code "120") (name "T28+") (class "Default")
      (node (ref "J$6") (pin "6") (pinfunction "6_6") (pintype "passive"))
      (node (ref "L55") (pin "2") (pinfunction "2_2") (pintype "passive"))
    )
    (net (code "121") (name "T28-") (class "Default")
      (node (ref "J$6") (pin "5") (pinfunction "5_5") (pintype "passive"))
      (node (ref "L56") (pin "2") (pinfunction "2_2") (pintype "passive"))
    )
    (net (code "122") (name "T29+") (class "Default")
      (node (ref "J$6") (pin "4") (pinfunction "4_4") (pintype "passive"))
      (node (ref "L57") (pin "2") (pinfunction "2_2") (pintype "passive"))
    )
    (net (code "123") (name "T29-") (class "Default")
      (node (ref "J$6") (pin "3") (pinfunction "3_3") (pintype "passive"))
      (node (ref "L58") (pin "2") (pinfunction "2_2") (pintype "passive"))
    )
    (net (code "124") (name "T30+") (class "Default")
      (node (ref "J$6") (pin "2") (pinfunction "2_2") (pintype "passive"))
      (node (ref "L59") (pin "2") (pinfunction "2_2") (pintype "passive"))
    )
    (net (code "125") (name "T30-") (class "Default")
      (node (ref "J$6") (pin "1") (pinfunction "1_1") (pintype "passive"))
      (node (ref "L60") (pin "2") (pinfunction "2_2") (pintype "passive"))
    )
    (net (code "126") (name "TEMP") (class "Default")
      (node (ref "J$1") (pin "5") (pinfunction "5_5") (pintype "passive"))
      (node (ref "U1") (pin "1") (pinfunction "DQ_1") (pintype "bidirectional"))
      (node (ref "U2") (pin "1") (pinfunction "DQ_1") (pintype "bidirectional"))
      (node (ref "U3") (pin "1") (pinfunction "DQ_1") (pintype "bidirectional"))
      (node (ref "U4") (pin "1") (pinfunction "DQ_1") (pintype "bidirectional"))
    )
    (net (code "127") (name "unconnected-(H1-MOUNT-PadB3,2)") (class "Default")
      (node (ref "H1") (pin "B3,2") (pinfunction "MOUNT_B3,2") (pintype "passive"))
    )
    (net (code "128") (name "unconnected-(H2-MOUNT-PadB3,2)") (class "Default")
      (node (ref "H2") (pin "B3,2") (pinfunction "MOUNT_B3,2") (pintype "passive"))
    )
    (net (code "129") (name "unconnected-(H3-MOUNT-PadB3,2)") (class "Default")
      (node (ref "H3") (pin "B3,2") (pinfunction "MOUNT_B3,2") (pintype "passive"))
    )
    (net (code "130") (name "unconnected-(H4-MOUNT-PadB3,2)") (class "Default")
      (node (ref "H4") (pin "B3,2") (pinfunction "MOUNT_B3,2") (pintype "passive"))
    )
    (net (code "131") (name "unconnected-(J$1-Pad1)") (class "Default")
      (node (ref "J$1") (pin "1") (pinfunction "1_1") (pintype "passive"))
    )
    (net (code "132") (name "unconnected-(J$1-Pad2)") (class "Default")
      (node (ref "J$1") (pin "2") (pinfunction "2_2") (pintype "passive"))
    )
    (net (code "133") (name "unconnected-(J$1-Pad3)") (class "Default")
      (node (ref "J$1") (pin "3") (pinfunction "3_3") (pintype "passive"))
    )
    (net (code "134") (name "unconnected-(J$1-Pad4)") (class "Default")
      (node (ref "J$1") (pin "4") (pinfunction "4_4") (pintype "passive"))
    )
    (net (code "135") (name "unconnected-(U5-NC-Pad10)") (class "Default")
      (node (ref "U5") (pin "10") (pinfunction "NC_10") (pintype "no_connect"))
    )
    (net (code "136") (name "unconnected-(U6-NC-Pad10)") (class "Default")
      (node (ref "U6") (pin "10") (pinfunction "NC_10") (pintype "no_connect"))
    )
    (net (code "137") (name "unconnected-(U7-NC-Pad10)") (class "Default")
      (node (ref "U7") (pin "10") (pinfunction "NC_10") (pintype "no_connect"))
    )
    (net (code "138") (name "unconnected-(U8-NC-Pad10)") (class "Default")
      (node (ref "U8") (pin "10") (pinfunction "NC_10") (pintype "no_connect"))
    )
    (net (code "139") (name "unconnected-(U9-NC-Pad10)") (class "Default")
      (node (ref "U9") (pin "10") (pinfunction "NC_10") (pintype "no_connect"))
    )
    (net (code "140") (name "unconnected-(U10-NC-Pad10)") (class "Default")
      (node (ref "U10") (pin "10") (pinfunction "NC_10") (pintype "no_connect"))
    )
    (net (code "141") (name "unconnected-(U11-NC-Pad10)") (class "Default")
      (node (ref "U11") (pin "10") (pinfunction "NC_10") (pintype "no_connect"))
    )
    (net (code "142") (name "unconnected-(U12-NC-Pad10)") (class "Default")
      (node (ref "U12") (pin "10") (pinfunction "NC_10") (pintype "no_connect"))
    )
    (net (code "143") (name "unconnected-(U13-NC-Pad10)") (class "Default")
      (node (ref "U13") (pin "10") (pinfunction "NC_10") (pintype "no_connect"))
    )
    (net (code "144") (name "unconnected-(U14-NC-Pad10)") (class "Default")
      (node (ref "U14") (pin "10") (pinfunction "NC_10") (pintype "no_connect"))
    )
    (net (code "145") (name "unconnected-(U15-NC-Pad10)") (class "Default")
      (node (ref "U15") (pin "10") (pinfunction "NC_10") (pintype "no_connect"))
    )
    (net (code "146") (name "unconnected-(U16-NC-Pad10)") (class "Default")
      (node (ref "U16") (pin "10") (pinfunction "NC_10") (pintype "no_connect"))
    )
    (net (code "147") (name "unconnected-(U17-NC-Pad10)") (class "Default")
      (node (ref "U17") (pin "10") (pinfunction "NC_10") (pintype "no_connect"))
    )
    (net (code "148") (name "unconnected-(U18-NC-Pad10)") (class "Default")
      (node (ref "U18") (pin "10") (pinfunction "NC_10") (pintype "no_connect"))
    )
    (net (code "149") (name "unconnected-(U19-NC-Pad10)") (class "Default")
      (node (ref "U19") (pin "10") (pinfunction "NC_10") (pintype "no_connect"))
    )
    (net (code "150") (name "unconnected-(U20-NC-Pad10)") (class "Default")
      (node (ref "U20") (pin "10") (pinfunction "NC_10") (pintype "no_connect"))
    )
    (net (code "151") (name "unconnected-(U21-NC-Pad10)") (class "Default")
      (node (ref "U21") (pin "10") (pinfunction "NC_10") (pintype "no_connect"))
    )
    (net (code "152") (name "unconnected-(U22-NC-Pad10)") (class "Default")
      (node (ref "U22") (pin "10") (pinfunction "NC_10") (pintype "no_connect"))
    )
    (net (code "153") (name "unconnected-(U23-NC-Pad10)") (class "Default")
      (node (ref "U23") (pin "10") (pinfunction "NC_10") (pintype "no_connect"))
    )
    (net (code "154") (name "unconnected-(U24-NC-Pad10)") (class "Default")
      (node (ref "U24") (pin "10") (pinfunction "NC_10") (pintype "no_connect"))
    )
    (net (code "155") (name "unconnected-(U25-NC-Pad10)") (class "Default")
      (node (ref "U25") (pin "10") (pinfunction "NC_10") (pintype "no_connect"))
    )
    (net (code "156") (name "unconnected-(U26-NC-Pad10)") (class "Default")
      (node (ref "U26") (pin "10") (pinfunction "NC_10") (pintype "no_connect"))
    )
    (net (code "157") (name "unconnected-(U27-NC-Pad10)") (class "Default")
      (node (ref "U27") (pin "10") (pinfunction "NC_10") (pintype "no_connect"))
    )
    (net (code "158") (name "unconnected-(U28-NC-Pad10)") (class "Default")
      (node (ref "U28") (pin "10") (pinfunction "NC_10") (pintype "no_connect"))
    )
    (net (code "159") (name "unconnected-(U29-NC-Pad10)") (class "Default")
      (node (ref "U29") (pin "10") (pinfunction "NC_10") (pintype "no_connect"))
    )
    (net (code "160") (name "unconnected-(U30-NC-Pad10)") (class "Default")
      (node (ref "U30") (pin "10") (pinfunction "NC_10") (pintype "no_connect"))
    )
    (net (code "161") (name "unconnected-(U31-NC-Pad10)") (class "Default")
      (node (ref "U31") (pin "10") (pinfunction "NC_10") (pintype "no_connect"))
    )
    (net (code "162") (name "unconnected-(U32-NC-Pad10)") (class "Default")
      (node (ref "U32") (pin "10") (pinfunction "NC_10") (pintype "no_connect"))
    )
    (net (code "163") (name "unconnected-(U33-NC-Pad10)") (class "Default")
      (node (ref "U33") (pin "10") (pinfunction "NC_10") (pintype "no_connect"))
    )
    (net (code "164") (name "unconnected-(U34-NC-Pad10)") (class "Default")
      (node (ref "U34") (pin "10") (pinfunction "NC_10") (pintype "no_connect"))
    )
  )
)
